# MB_pl_io.net
KiCad netlist of a schematic drawn in Altium Designer
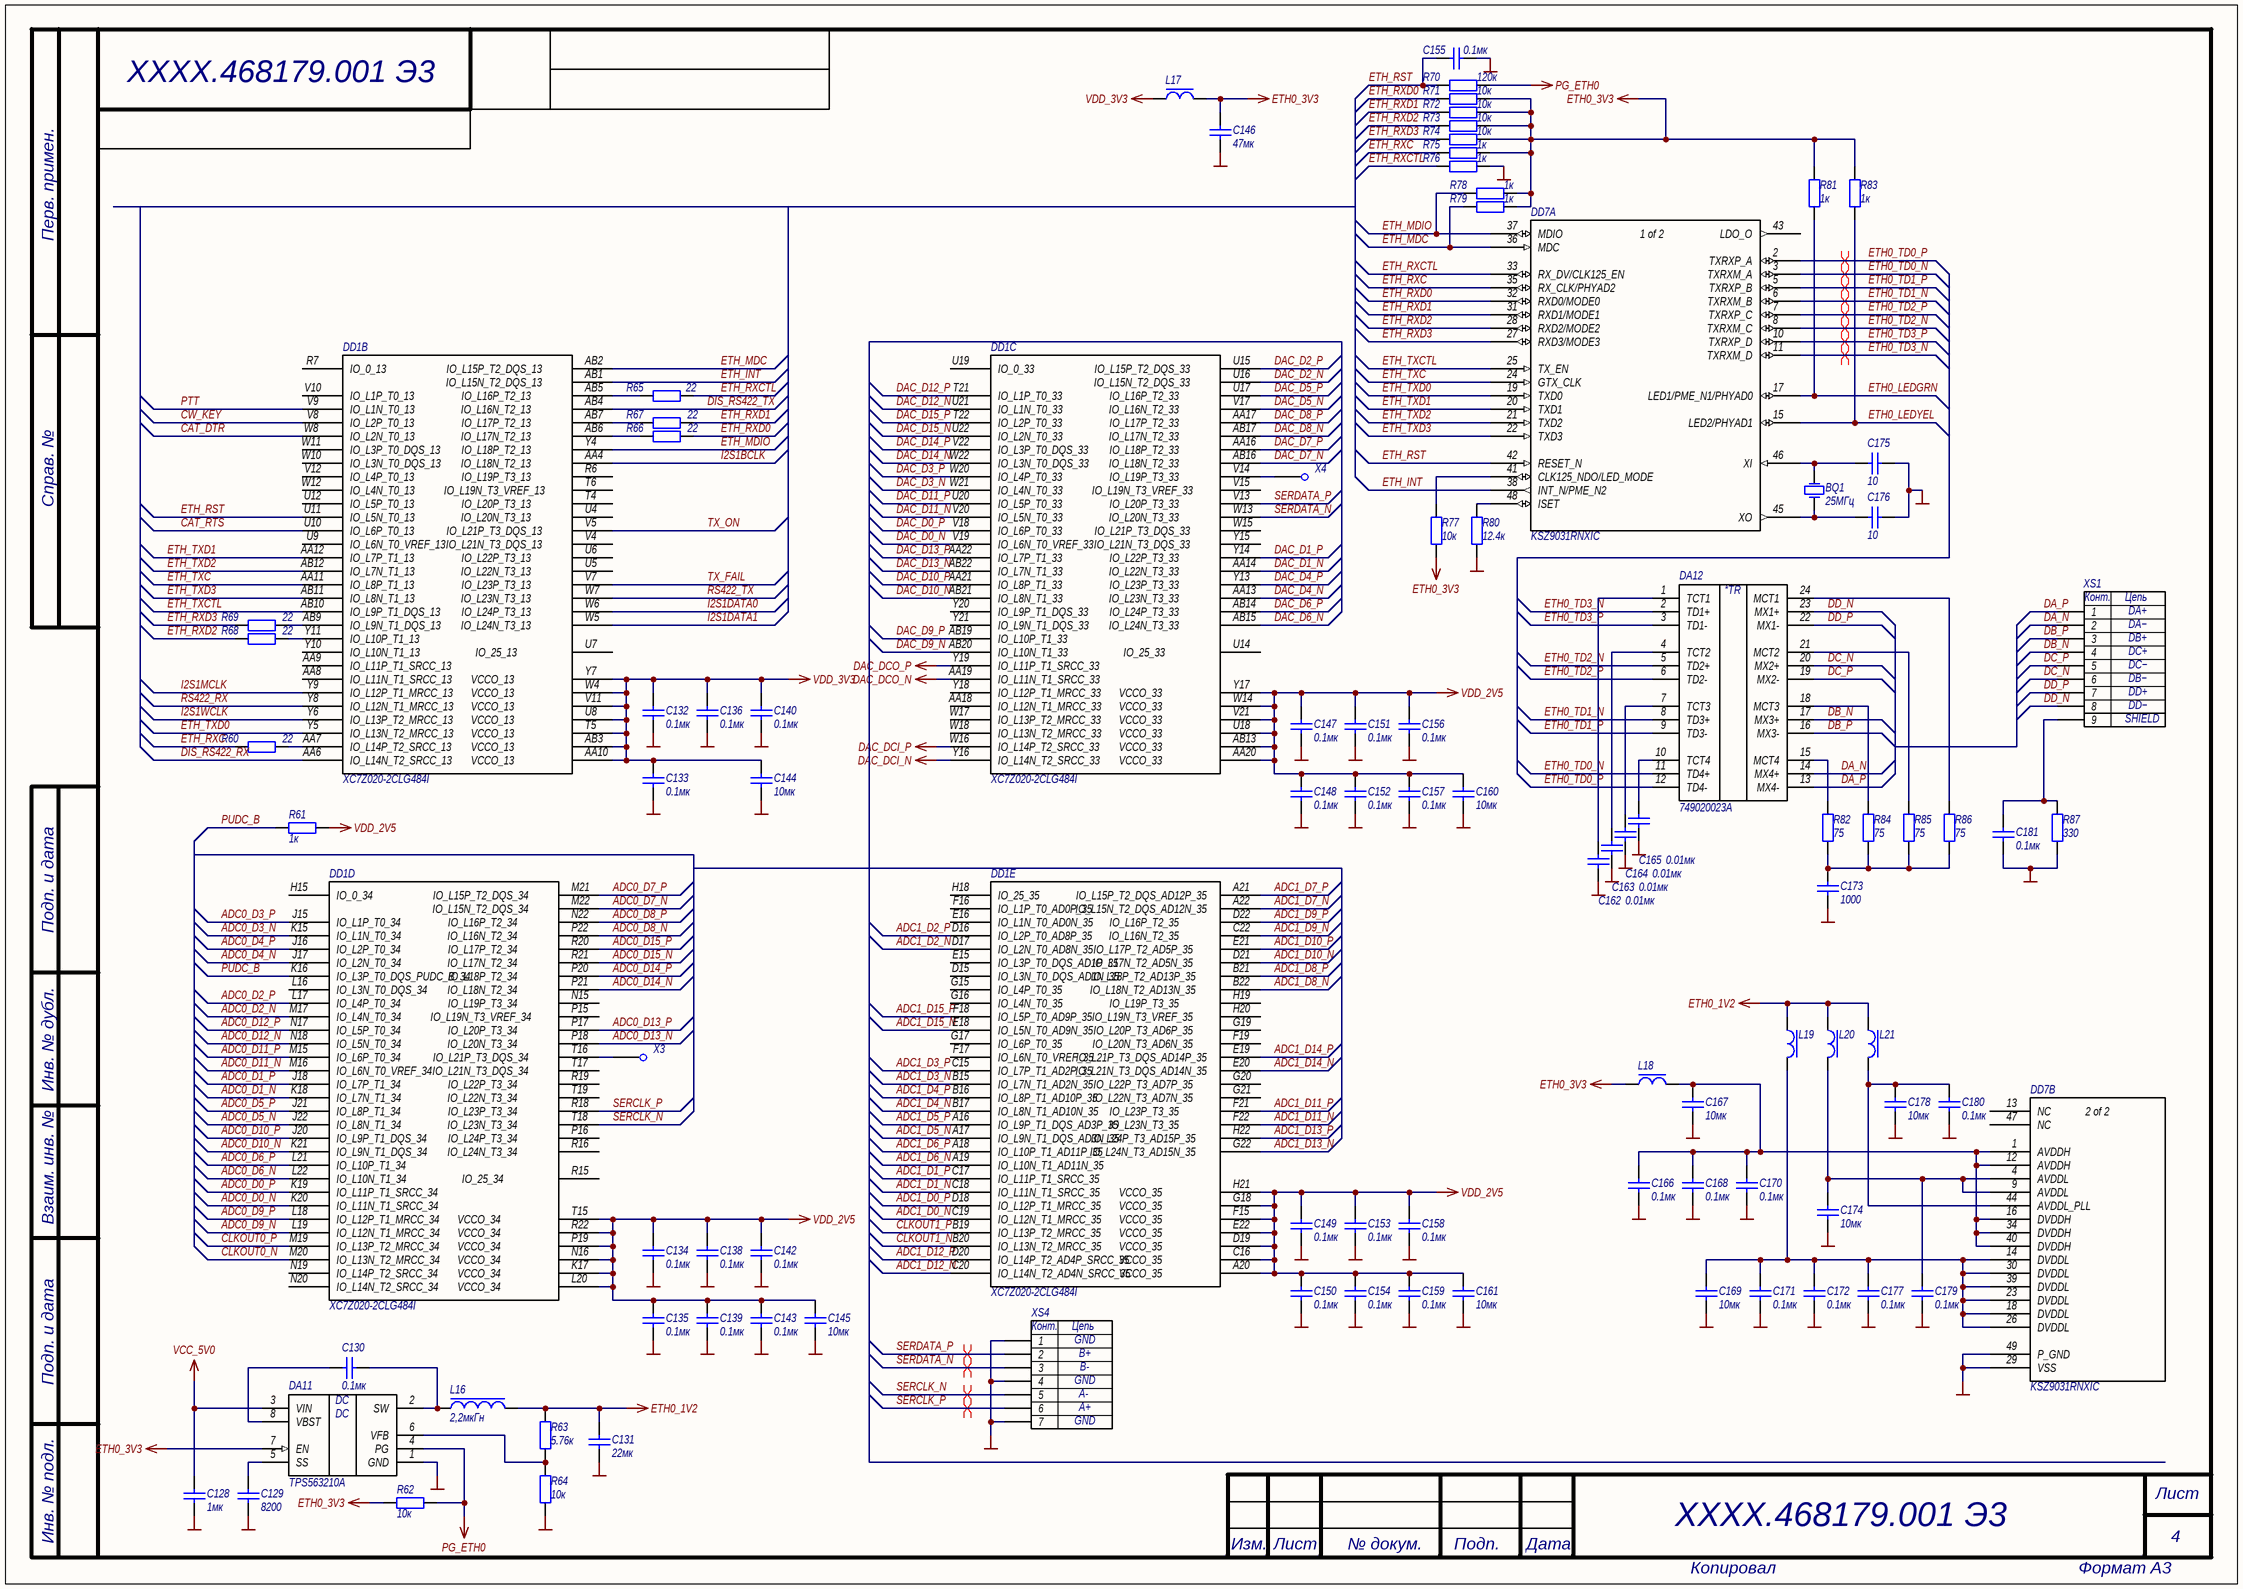
[diagram p0: MB_pl_io.SchDoc]

(export (version "E")
  (design (tool "Eeschema 10.0.6"))
  (components
    (comp (ref "BQ1")
      (value "25МГц")
      (footprint "ABRACOM ABM10")
      (description "Резонатор кварцевый")
      (fields (field (name "TOLERANCE") "±20 ppm") (field (name "MANUFACTURER") "ABRACON"))
      (libsource (lib "nels_other") (part "Кварц ABM10-25.000MHZ-D30"))
    )
    (comp (ref "C128")
      (value "1мк")
      (footprint "CAPC1005X06N")
      (description "Кер. ЧИП-конденсатор")
      (fields (field (name "TOLERANCE") "±10%"))
      (libsource (lib "nels_caps") (part "Кер.ЧИП конд. 0402 1мкФ X5R 10%, 10В"))
    )
    (comp (ref "C129")
      (value "8200")
      (footprint "CAPC1005X06N")
      (description "Кер. ЧИП-конденсатор")
      (fields (field (name "TOLERANCE") "±20%"))
      (libsource (lib "nels_caps") (part "Кер.ЧИП конд. 0402 8200пФ X7R 10%, 50В"))
    )
    (comp (ref "C130")
      (value "0.1мк")
      (footprint "CAPC1005X06N")
      (description "Кер. ЧИП-конденсатор")
      (fields (field (name "TOLERANCE") "±10%"))
      (libsource (lib "nels") (part "Кер.ЧИП конд. 0402 0.1мкФ X7R 10%, 16В"))
    )
    (comp (ref "C131")
      (value "22мк")
      (footprint "CAPC2012X12L")
      (description "Кер. ЧИП-конденсатор")
      (fields (field (name "MANUFACTURER") "TDK") (field (name "TOLERANCE") "±10%"))
      (libsource (lib "nels_caps") (part "Кер.ЧИП конд. 0805 22мкФ X5R 10% 16В"))
    )
    (comp (ref "C132")
      (value "0.1мк")
      (footprint "CAPC1005X06N")
      (description "Кер. ЧИП-конденсатор")
      (fields (field (name "TOLERANCE") "±10%"))
      (libsource (lib "nels") (part "Кер.ЧИП конд. 0402 0.1мкФ X7R 10%, 16В"))
    )
    (comp (ref "C133")
      (value "0.1мк")
      (footprint "CAPC1005X06N")
      (description "Кер. ЧИП-конденсатор")
      (fields (field (name "TOLERANCE") "±10%"))
      (libsource (lib "nels") (part "Кер.ЧИП конд. 0402 0.1мкФ X7R 10%, 16В"))
    )
    (comp (ref "C134")
      (value "0.1мк")
      (footprint "CAPC1005X06N")
      (description "Кер. ЧИП-конденсатор")
      (fields (field (name "TOLERANCE") "±10%"))
      (libsource (lib "nels") (part "Кер.ЧИП конд. 0402 0.1мкФ X7R 10%, 16В"))
    )
    (comp (ref "C135")
      (value "0.1мк")
      (footprint "CAPC1005X06N")
      (description "Кер. ЧИП-конденсатор")
      (fields (field (name "TOLERANCE") "±10%"))
      (libsource (lib "nels") (part "Кер.ЧИП конд. 0402 0.1мкФ X7R 10%, 16В"))
    )
    (comp (ref "C136")
      (value "0.1мк")
      (footprint "CAPC1005X06N")
      (description "Кер. ЧИП-конденсатор")
      (fields (field (name "TOLERANCE") "±10%"))
      (libsource (lib "nels") (part "Кер.ЧИП конд. 0402 0.1мкФ X7R 10%, 16В"))
    )
    (comp (ref "C138")
      (value "0.1мк")
      (footprint "CAPC1005X06N")
      (description "Кер. ЧИП-конденсатор")
      (fields (field (name "TOLERANCE") "±10%"))
      (libsource (lib "nels") (part "Кер.ЧИП конд. 0402 0.1мкФ X7R 10%, 16В"))
    )
    (comp (ref "C139")
      (value "0.1мк")
      (footprint "CAPC1005X06N")
      (description "Кер. ЧИП-конденсатор")
      (fields (field (name "TOLERANCE") "±10%"))
      (libsource (lib "nels") (part "Кер.ЧИП конд. 0402 0.1мкФ X7R 10%, 16В"))
    )
    (comp (ref "C140")
      (value "0.1мк")
      (footprint "CAPC1005X06N")
      (description "Кер. ЧИП-конденсатор")
      (fields (field (name "TOLERANCE") "±10%"))
      (libsource (lib "nels") (part "Кер.ЧИП конд. 0402 0.1мкФ X7R 10%, 16В"))
    )
    (comp (ref "C142")
      (value "0.1мк")
      (footprint "CAPC1005X06N")
      (description "Кер. ЧИП-конденсатор")
      (fields (field (name "TOLERANCE") "±10%"))
      (libsource (lib "nels") (part "Кер.ЧИП конд. 0402 0.1мкФ X7R 10%, 16В"))
    )
    (comp (ref "C143")
      (value "0.1мк")
      (footprint "CAPC1005X06N")
      (description "Кер. ЧИП-конденсатор")
      (fields (field (name "TOLERANCE") "±10%"))
      (libsource (lib "nels") (part "Кер.ЧИП конд. 0402 0.1мкФ X7R 10%, 16В"))
    )
    (comp (ref "C144")
      (value "10мк")
      (footprint "CAPC1608X08L")
      (description "Кер. ЧИП-конденсатор")
      (fields (field (name "MANUFACTURER") "Murata") (field (name "TOLERANCE") "±20%"))
      (libsource (lib "nels_caps") (part "Кер.ЧИП конд. 0603 10мкФ X5R 20% 6.3В"))
    )
    (comp (ref "C145")
      (value "10мк")
      (footprint "CAPC1608X08L")
      (description "Кер. ЧИП-конденсатор")
      (fields (field (name "MANUFACTURER") "Murata") (field (name "TOLERANCE") "±20%"))
      (libsource (lib "nels_caps") (part "Кер.ЧИП конд. 0603 10мкФ X5R 20% 6.3В"))
    )
    (comp (ref "C146")
      (value "47мк")
      (footprint "CAPC2012X12L")
      (description "Кер. ЧИП-конденсатор")
      (fields (field (name "MANUFACTURER") "Murata") (field (name "TOLERANCE") "±20%"))
      (libsource (lib "nels_caps") (part "Кер.ЧИП конд. 0805 47мкФ X5R 20% 10В"))
    )
    (comp (ref "C147")
      (value "0.1мк")
      (footprint "CAPC1005X06N")
      (description "Кер. ЧИП-конденсатор")
      (fields (field (name "TOLERANCE") "±10%"))
      (libsource (lib "nels") (part "Кер.ЧИП конд. 0402 0.1мкФ X7R 10%, 16В"))
    )
    (comp (ref "C148")
      (value "0.1мк")
      (footprint "CAPC1005X06N")
      (description "Кер. ЧИП-конденсатор")
      (fields (field (name "TOLERANCE") "±10%"))
      (libsource (lib "nels") (part "Кер.ЧИП конд. 0402 0.1мкФ X7R 10%, 16В"))
    )
    (comp (ref "C149")
      (value "0.1мк")
      (footprint "CAPC1005X06N")
      (description "Кер. ЧИП-конденсатор")
      (fields (field (name "TOLERANCE") "±10%"))
      (libsource (lib "nels") (part "Кер.ЧИП конд. 0402 0.1мкФ X7R 10%, 16В"))
    )
    (comp (ref "C150")
      (value "0.1мк")
      (footprint "CAPC1005X06N")
      (description "Кер. ЧИП-конденсатор")
      (fields (field (name "TOLERANCE") "±10%"))
      (libsource (lib "nels") (part "Кер.ЧИП конд. 0402 0.1мкФ X7R 10%, 16В"))
    )
    (comp (ref "C151")
      (value "0.1мк")
      (footprint "CAPC1005X06N")
      (description "Кер. ЧИП-конденсатор")
      (fields (field (name "TOLERANCE") "±10%"))
      (libsource (lib "nels") (part "Кер.ЧИП конд. 0402 0.1мкФ X7R 10%, 16В"))
    )
    (comp (ref "C152")
      (value "0.1мк")
      (footprint "CAPC1005X06N")
      (description "Кер. ЧИП-конденсатор")
      (fields (field (name "TOLERANCE") "±10%"))
      (libsource (lib "nels") (part "Кер.ЧИП конд. 0402 0.1мкФ X7R 10%, 16В"))
    )
    (comp (ref "C153")
      (value "0.1мк")
      (footprint "CAPC1005X06N")
      (description "Кер. ЧИП-конденсатор")
      (fields (field (name "TOLERANCE") "±10%"))
      (libsource (lib "nels") (part "Кер.ЧИП конд. 0402 0.1мкФ X7R 10%, 16В"))
    )
    (comp (ref "C154")
      (value "0.1мк")
      (footprint "CAPC1005X06N")
      (description "Кер. ЧИП-конденсатор")
      (fields (field (name "TOLERANCE") "±10%"))
      (libsource (lib "nels") (part "Кер.ЧИП конд. 0402 0.1мкФ X7R 10%, 16В"))
    )
    (comp (ref "C155")
      (value "0.1мк")
      (footprint "CAPC1005X06N")
      (description "Кер. ЧИП-конденсатор")
      (fields (field (name "TOLERANCE") "±10%"))
      (libsource (lib "nels") (part "Кер.ЧИП конд. 0402 0.1мкФ X7R 10%, 16В"))
    )
    (comp (ref "C156")
      (value "0.1мк")
      (footprint "CAPC1005X06N")
      (description "Кер. ЧИП-конденсатор")
      (fields (field (name "TOLERANCE") "±10%"))
      (libsource (lib "nels") (part "Кер.ЧИП конд. 0402 0.1мкФ X7R 10%, 16В"))
    )
    (comp (ref "C157")
      (value "0.1мк")
      (footprint "CAPC1005X06N")
      (description "Кер. ЧИП-конденсатор")
      (fields (field (name "TOLERANCE") "±10%"))
      (libsource (lib "nels") (part "Кер.ЧИП конд. 0402 0.1мкФ X7R 10%, 16В"))
    )
    (comp (ref "C158")
      (value "0.1мк")
      (footprint "CAPC1005X06N")
      (description "Кер. ЧИП-конденсатор")
      (fields (field (name "TOLERANCE") "±10%"))
      (libsource (lib "nels") (part "Кер.ЧИП конд. 0402 0.1мкФ X7R 10%, 16В"))
    )
    (comp (ref "C159")
      (value "0.1мк")
      (footprint "CAPC1005X06N")
      (description "Кер. ЧИП-конденсатор")
      (fields (field (name "TOLERANCE") "±10%"))
      (libsource (lib "nels") (part "Кер.ЧИП конд. 0402 0.1мкФ X7R 10%, 16В"))
    )
    (comp (ref "C160")
      (value "10мк")
      (footprint "CAPC1608X08L")
      (description "Кер. ЧИП-конденсатор")
      (fields (field (name "MANUFACTURER") "Murata") (field (name "TOLERANCE") "±20%"))
      (libsource (lib "nels_caps") (part "Кер.ЧИП конд. 0603 10мкФ X5R 20% 6.3В"))
    )
    (comp (ref "C161")
      (value "10мк")
      (footprint "CAPC1608X08L")
      (description "Кер. ЧИП-конденсатор")
      (fields (field (name "MANUFACTURER") "Murata") (field (name "TOLERANCE") "±20%"))
      (libsource (lib "nels_caps") (part "Кер.ЧИП конд. 0603 10мкФ X5R 20% 6.3В"))
    )
    (comp (ref "C162")
      (value "0.01мк")
      (footprint "CAPC1005X06N")
      (description "Кер. ЧИП-конденсатор")
      (fields (field (name "TOLERANCE") "±20%"))
      (libsource (lib "nels_caps") (part "Кер.ЧИП конд. 0402 0.01мкФ X7R 10%, 50В"))
    )
    (comp (ref "C163")
      (value "0.01мк")
      (footprint "CAPC1005X06N")
      (description "Кер. ЧИП-конденсатор")
      (fields (field (name "TOLERANCE") "±20%"))
      (libsource (lib "nels_caps") (part "Кер.ЧИП конд. 0402 0.01мкФ X7R 10%, 50В"))
    )
    (comp (ref "C164")
      (value "0.01мк")
      (footprint "CAPC1005X06N")
      (description "Кер. ЧИП-конденсатор")
      (fields (field (name "TOLERANCE") "±20%"))
      (libsource (lib "nels_caps") (part "Кер.ЧИП конд. 0402 0.01мкФ X7R 10%, 50В"))
    )
    (comp (ref "C165")
      (value "0.01мк")
      (footprint "CAPC1005X06N")
      (description "Кер. ЧИП-конденсатор")
      (fields (field (name "TOLERANCE") "±20%"))
      (libsource (lib "nels_caps") (part "Кер.ЧИП конд. 0402 0.01мкФ X7R 10%, 50В"))
    )
    (comp (ref "C166")
      (value "0.1мк")
      (footprint "CAPC1005X06N")
      (description "Кер. ЧИП-конденсатор")
      (fields (field (name "TOLERANCE") "±10%"))
      (libsource (lib "nels_caps") (part "Кер.ЧИП конд. 0402 0.1мкФ X7R 10%, 16В"))
    )
    (comp (ref "C167")
      (value "10мк")
      (footprint "CAPC1608X08L")
      (description "Кер. ЧИП-конденсатор")
      (fields (field (name "MANUFACTURER") "Murata") (field (name "TOLERANCE") "±20%"))
      (libsource (lib "nels_caps") (part "Кер.ЧИП конд. 0603 10мкФ X5R 20% 6.3В"))
    )
    (comp (ref "C168")
      (value "0.1мк")
      (footprint "CAPC1005X06N")
      (description "Кер. ЧИП-конденсатор")
      (fields (field (name "TOLERANCE") "±10%"))
      (libsource (lib "nels_caps") (part "Кер.ЧИП конд. 0402 0.1мкФ X7R 10%, 16В"))
    )
    (comp (ref "C169")
      (value "10мк")
      (footprint "CAPC1608X08L")
      (description "Кер. ЧИП-конденсатор")
      (fields (field (name "MANUFACTURER") "Murata") (field (name "TOLERANCE") "±20%"))
      (libsource (lib "nels_caps") (part "Кер.ЧИП конд. 0603 10мкФ X5R 20% 6.3В"))
    )
    (comp (ref "C170")
      (value "0.1мк")
      (footprint "CAPC1005X06N")
      (description "Кер. ЧИП-конденсатор")
      (fields (field (name "TOLERANCE") "±10%"))
      (libsource (lib "nels_caps") (part "Кер.ЧИП конд. 0402 0.1мкФ X7R 10%, 16В"))
    )
    (comp (ref "C171")
      (value "0.1мк")
      (footprint "CAPC1005X06N")
      (description "Кер. ЧИП-конденсатор")
      (fields (field (name "TOLERANCE") "±10%"))
      (libsource (lib "nels_caps") (part "Кер.ЧИП конд. 0402 0.1мкФ X7R 10%, 16В"))
    )
    (comp (ref "C172")
      (value "0.1мк")
      (footprint "CAPC1005X06N")
      (description "Кер. ЧИП-конденсатор")
      (fields (field (name "TOLERANCE") "±10%"))
      (libsource (lib "nels_caps") (part "Кер.ЧИП конд. 0402 0.1мкФ X7R 10%, 16В"))
    )
    (comp (ref "C173")
      (value "1000")
      (footprint "CAPC1005X06N")
      (description "Кер. ЧИП-конденсатор")
      (fields (field (name "TOLERANCE") "±5%"))
      (libsource (lib "nels_caps") (part "Кер.ЧИП конд. 0402 1000пФ NP0 5%, 50В"))
    )
    (comp (ref "C174")
      (value "10мк")
      (footprint "CAPC1608X08L")
      (description "Кер. ЧИП-конденсатор")
      (fields (field (name "MANUFACTURER") "Murata") (field (name "TOLERANCE") "±20%"))
      (libsource (lib "nels_caps") (part "Кер.ЧИП конд. 0603 10мкФ X5R 20% 6.3В"))
    )
    (comp (ref "C175")
      (value "10")
      (footprint "CAPC1005X06N")
      (description "Кер. ЧИП-конденсатор")
      (fields (field (name "TOLERANCE") "±5%"))
      (libsource (lib "nels_caps") (part "Кер.ЧИП конд. 0402 10пФ NPO 5%, 50В"))
    )
    (comp (ref "C176")
      (value "10")
      (footprint "CAPC1005X06N")
      (description "Кер. ЧИП-конденсатор")
      (fields (field (name "TOLERANCE") "±5%"))
      (libsource (lib "nels_caps") (part "Кер.ЧИП конд. 0402 10пФ NPO 5%, 50В"))
    )
    (comp (ref "C177")
      (value "0.1мк")
      (footprint "CAPC1005X06N")
      (description "Кер. ЧИП-конденсатор")
      (fields (field (name "TOLERANCE") "±10%"))
      (libsource (lib "nels_caps") (part "Кер.ЧИП конд. 0402 0.1мкФ X7R 10%, 16В"))
    )
    (comp (ref "C178")
      (value "10мк")
      (footprint "CAPC1608X08L")
      (description "Кер. ЧИП-конденсатор")
      (fields (field (name "MANUFACTURER") "Murata") (field (name "TOLERANCE") "±20%"))
      (libsource (lib "nels_caps") (part "Кер.ЧИП конд. 0603 10мкФ X5R 20% 6.3В"))
    )
    (comp (ref "C179")
      (value "0.1мк")
      (footprint "CAPC1005X06N")
      (description "Кер. ЧИП-конденсатор")
      (fields (field (name "TOLERANCE") "±10%"))
      (libsource (lib "nels_caps") (part "Кер.ЧИП конд. 0402 0.1мкФ X7R 10%, 16В"))
    )
    (comp (ref "C180")
      (value "0.1мк")
      (footprint "CAPC1005X06N")
      (description "Кер. ЧИП-конденсатор")
      (fields (field (name "TOLERANCE") "±10%"))
      (libsource (lib "nels_caps") (part "Кер.ЧИП конд. 0402 0.1мкФ X7R 10%, 16В"))
    )
    (comp (ref "C181")
      (value "0.1мк")
      (footprint "CAPC1608X08L")
      (description "Кер. ЧИП-конденсатор")
      (fields (field (name "TOLERANCE") "±10%") (field (name "MANUFACTURER") "Murata"))
      (libsource (lib "nels_caps") (part "Кер.ЧИП конд. 0603 0.1мкФ X7R 10% 50В"))
    )
    (comp (ref "DA11")
      (value "TPS563210A")
      (footprint "TSOP65P280X110-8N")
      (description "TPS56x210A, 4.5-V to 17-V Input, 2-A, 3-A Synchrono")
      (fields (field (name "MANUFACTURER") "TI"))
      (libsource (lib "MB") (part "Микросхема TPS563210A"))
    )
    (comp (ref "DA12")
      (value "749020023A")
      (footprint "749020023A")
      (description "1000BASE-T Magnetics Module")
      (fields (field (name "MANUFACTURER") "Wurth Elektronik"))
      (libsource (lib "nels_other") (part "Сборка трансформаторов 749020023A"))
    )
    (comp (ref "DD1")
      (value "XC7Z020-2CLG484I")
      (footprint "BGA484C80P22X22_1900X1900X160")
      (description "Zynq®-7000 SoC Family")
      (fields (field (name "MANUFACTURER") "XILINX"))
      (libsource (lib "MB") (part "Микросхема XC7Z020-2CLG484I"))
    )
    (comp (ref "DD7")
      (value "KSZ9031RNXIC")
      (footprint "QFN50P700X700-48V6M")
      (description "Gigabit Ethernet Transceiver with Power Saving Features")
      (fields (field (name "COPYRIGHT") "Copyright (C) 2018 Accelerated Designs. All rights reserved"))
      (libsource (lib "nels_chip") (part "Микросхема KSZ9031RNXIC"))
    )
    (comp (ref "L16")
      (value "2,2мкГн")
      (footprint "CSAB0420")
      (description "Molding Power Choke")
      (fields
        (field (name "MANUFACTURER") "Vishay")
        (field (name "MANUFACTURERPARTNUMBER") "IHLP1616ABER1R0M11")
      )
      (libsource (lib "nels_ind") (part "ЧИП индуктивность CSAB0420-2R2M"))
    )
    (comp (ref "L17")
      (value "BLM18PG121SN1D")
      (footprint "INDC1608X08L")
      (description "SMD EMI Suppression Filter EMIFIL")
      (fields (field (name "MANUFACTURER") "Murata"))
      (libsource (lib "nels_ind") (part "ЧИП дроссель 0603 BLM18PG121SN1D"))
    )
    (comp (ref "L18")
      (value "BLM18PG121SN1D")
      (footprint "INDC1608X08L")
      (description "SMD EMI Suppression Filter EMIFIL")
      (fields (field (name "MANUFACTURER") "Murata"))
      (libsource (lib "nels_ind") (part "ЧИП дроссель 0603 BLM18PG121SN1D"))
    )
    (comp (ref "L19")
      (value "BLM18PG121SN1D")
      (footprint "INDC1608X08L")
      (description "SMD EMI Suppression Filter EMIFIL")
      (fields (field (name "MANUFACTURER") "Murata"))
      (libsource (lib "nels_ind") (part "ЧИП дроссель 0603 BLM18PG121SN1D"))
    )
    (comp (ref "L20")
      (value "BLM18PG121SN1D")
      (footprint "INDC1608X08L")
      (description "SMD EMI Suppression Filter EMIFIL")
      (fields (field (name "MANUFACTURER") "Murata"))
      (libsource (lib "nels_ind") (part "ЧИП дроссель 0603 BLM18PG121SN1D"))
    )
    (comp (ref "L21")
      (value "BLM18PG121SN1D")
      (footprint "INDC1608X08L")
      (description "SMD EMI Suppression Filter EMIFIL")
      (fields (field (name "MANUFACTURER") "Murata"))
      (libsource (lib "nels_ind") (part "ЧИП дроссель 0603 BLM18PG121SN1D"))
    )
    (comp (ref "R60")
      (value "22")
      (footprint "RESC1005X06N")
      (description "ЧИП-резистор")
      (fields (field (name "TOLERANCE") "±5%"))
      (libsource (lib "nels_res") (part "Чип резистор 0402 22 Ом, 5%"))
    )
    (comp (ref "R61")
      (value "1к")
      (footprint "RESC1005X06N")
      (description "ЧИП-резистор")
      (fields (field (name "TOLERANCE") "±5%"))
      (libsource (lib "") (part "Чип резистор 0402 1 кОм, 5%_1"))
    )
    (comp (ref "R62")
      (value "10к")
      (footprint "RESC1005X06N")
      (description "ЧИП-резистор")
      (fields (field (name "TOLERANCE") "±5%"))
      (libsource (lib "nels_res") (part "Чип резистор 0402 10 кОм, 1%"))
    )
    (comp (ref "R63")
      (value "5.76к")
      (footprint "RESC1005X06N")
      (description "ЧИП-резистор")
      (fields (field (name "TOLERANCE") "±1%"))
      (libsource (lib "nels_res") (part "Чип резистор 0402 5,76 кОм, 1%"))
    )
    (comp (ref "R64")
      (value "10к")
      (footprint "RESC1005X06N")
      (description "ЧИП-резистор")
      (fields (field (name "TOLERANCE") "±5%"))
      (libsource (lib "nels_res") (part "Чип резистор 0402 10 кОм, 5%"))
    )
    (comp (ref "R65")
      (value "22")
      (footprint "RESC1005X06N")
      (description "ЧИП-резистор")
      (fields (field (name "TOLERANCE") "±5%"))
      (libsource (lib "") (part "Чип резистор 0402 22 Ом, 5%_1"))
    )
    (comp (ref "R66")
      (value "22")
      (footprint "RESC1005X06N")
      (description "ЧИП-резистор")
      (fields (field (name "TOLERANCE") "±5%"))
      (libsource (lib "nels_res") (part "Чип резистор 0402 22 Ом, 5%"))
    )
    (comp (ref "R67")
      (value "22")
      (footprint "RESC1005X06N")
      (description "ЧИП-резистор")
      (fields (field (name "TOLERANCE") "±5%"))
      (libsource (lib "nels_res") (part "Чип резистор 0402 22 Ом, 5%"))
    )
    (comp (ref "R68")
      (value "22")
      (footprint "RESC1005X06N")
      (description "ЧИП-резистор")
      (fields (field (name "TOLERANCE") "±5%"))
      (libsource (lib "nels_res") (part "Чип резистор 0402 22 Ом, 5%"))
    )
    (comp (ref "R69")
      (value "22")
      (footprint "RESC1005X06N")
      (description "ЧИП-резистор")
      (fields (field (name "TOLERANCE") "±5%"))
      (libsource (lib "nels_res") (part "Чип резистор 0402 22 Ом, 5%"))
    )
    (comp (ref "R70")
      (value "120к")
      (footprint "RESC1005X06N")
      (description "ЧИП-резистор")
      (fields (field (name "TOLERANCE") "±5%"))
      (libsource (lib "nels_res") (part "Чип резистор 0402 120 кОм, 5%"))
    )
    (comp (ref "R71")
      (value "10к")
      (footprint "RESC1005X06N")
      (description "ЧИП-резистор")
      (fields (field (name "TOLERANCE") "±5%"))
      (libsource (lib "") (part "Чип резистор 0402 10 кОм, 5%_1"))
    )
    (comp (ref "R72")
      (value "10к")
      (footprint "RESC1005X06N")
      (description "ЧИП-резистор")
      (fields (field (name "TOLERANCE") "±5%"))
      (libsource (lib "") (part "Чип резистор 0402 10 кОм, 5%_1"))
    )
    (comp (ref "R73")
      (value "10к")
      (footprint "RESC1005X06N")
      (description "ЧИП-резистор")
      (fields (field (name "TOLERANCE") "±5%"))
      (libsource (lib "") (part "Чип резистор 0402 10 кОм, 5%_1"))
    )
    (comp (ref "R74")
      (value "10к")
      (footprint "RESC1005X06N")
      (description "ЧИП-резистор")
      (fields (field (name "TOLERANCE") "±5%"))
      (libsource (lib "") (part "Чип резистор 0402 10 кОм, 5%_1"))
    )
    (comp (ref "R75")
      (value "1к")
      (footprint "RESC1005X06N")
      (description "ЧИП-резистор")
      (fields (field (name "TOLERANCE") "±5%"))
      (libsource (lib "") (part "Чип резистор 0402 1 кОм, 5%_1"))
    )
    (comp (ref "R76")
      (value "1к")
      (footprint "RESC1005X06N")
      (description "ЧИП-резистор")
      (fields (field (name "TOLERANCE") "±5%"))
      (libsource (lib "") (part "Чип резистор 0402 1 кОм, 5%_1"))
    )
    (comp (ref "R77")
      (value "10к")
      (footprint "RESC1005X06N")
      (description "ЧИП-резистор")
      (fields (field (name "TOLERANCE") "±5%"))
      (libsource (lib "nels_res") (part "Чип резистор 0402 10 кОм, 5%"))
    )
    (comp (ref "R78")
      (value "1к")
      (footprint "RESC1005X06N")
      (description "ЧИП-резистор")
      (fields (field (name "TOLERANCE") "±5%"))
      (libsource (lib "") (part "Чип резистор 0402 1 кОм, 5%_1"))
    )
    (comp (ref "R79")
      (value "1к")
      (footprint "RESC1005X06N")
      (description "ЧИП-резистор")
      (fields (field (name "TOLERANCE") "±5%"))
      (libsource (lib "") (part "Чип резистор 0402 1 кОм, 5%_1"))
    )
    (comp (ref "R80")
      (value "12.4к")
      (footprint "RESC1005X06N")
      (description "ЧИП-резистор")
      (fields (field (name "TOLERANCE") "±1%"))
      (libsource (lib "nels_res") (part "Чип резистор 0402 12.4 кОм, 1%"))
    )
    (comp (ref "R81")
      (value "1к")
      (footprint "RESC1005X06N")
      (description "ЧИП-резистор")
      (fields (field (name "TOLERANCE") "±5%"))
      (libsource (lib "nels_res") (part "Чип резистор 0402 1 кОм, 5%"))
    )
    (comp (ref "R82")
      (value "75")
      (footprint "RESC1005X06N")
      (description "ЧИП-резистор")
      (fields (field (name "TOLERANCE") "±5%"))
      (libsource (lib "nels_res") (part "Чип резистор 0402 75 Ом, 5%"))
    )
    (comp (ref "R83")
      (value "1к")
      (footprint "RESC1005X06N")
      (description "ЧИП-резистор")
      (fields (field (name "TOLERANCE") "±5%"))
      (libsource (lib "nels_res") (part "Чип резистор 0402 1 кОм, 5%"))
    )
    (comp (ref "R84")
      (value "75")
      (footprint "RESC1005X06N")
      (description "ЧИП-резистор")
      (fields (field (name "TOLERANCE") "±5%"))
      (libsource (lib "nels_res") (part "Чип резистор 0402 75 Ом, 5%"))
    )
    (comp (ref "R85")
      (value "75")
      (footprint "RESC1005X06N")
      (description "ЧИП-резистор")
      (fields (field (name "TOLERANCE") "±5%"))
      (libsource (lib "nels_res") (part "Чип резистор 0402 75 Ом, 5%"))
    )
    (comp (ref "R86")
      (value "75")
      (footprint "RESC1005X06N")
      (description "ЧИП-резистор")
      (fields (field (name "TOLERANCE") "±5%"))
      (libsource (lib "nels_res") (part "Чип резистор 0402 75 Ом, 5%"))
    )
    (comp (ref "R87")
      (value "330")
      (footprint "RESC1005X06N")
      (description "ЧИП-резистор")
      (fields (field (name "TOLERANCE") "±5%"))
      (libsource (lib "nels_res") (part "Чип резистор 0402 330 Ом, 5%"))
    )
    (comp (ref "X3")
      (value "Конструктивный элемент")
      (footprint "PIN2_PROBE")
      (description "Соединитель")
      (libsource (lib "nels_conn") (part "Соединение под пайку"))
    )
    (comp (ref "X4")
      (value "Конструктивный элемент")
      (footprint "PIN2_PROBE")
      (description "Соединитель")
      (libsource (lib "nels_conn") (part "Соединение под пайку"))
    )
    (comp (ref "XS1")
      (value "TJ16S-8P8C")
      (footprint "KLS12-107L")
      (description "Modular Jack RJ45")
      (fields (field (name "MANUFACTURER") "KLS"))
      (libsource (lib "nels_conn") (part "Соединитель KLS12-107L-2-8P8C-0"))
    )
    (comp (ref "XS4")
      (value "KLS1-SATA001")
      (footprint "KLS1-SATA001")
      (description "SATA Type A 7P Male Connector,SMD")
      (fields (field (name "MANUFACTURER") "KLS"))
      (libsource (lib "nels_conn") (part "Соединитель KLS1-SATA001"))
    )
  )
  (nets
    (net (code "1") (name "/ADC0_D0_N") (class "Default")
      (node (ref "DD1") (pin "K20") (pinfunction "IO_L11N_T1_SRCC_34_K20") (pintype "passive"))
    )
    (net (code "2") (name "/ADC0_D0_P") (class "Default")
      (node (ref "DD1") (pin "K19") (pinfunction "IO_L11P_T1_SRCC_34_K19") (pintype "passive"))
    )
    (net (code "3") (name "/ADC0_D1_N") (class "Default")
      (node (ref "DD1") (pin "K18") (pinfunction "IO_L7N_T1_34_K18") (pintype "passive"))
    )
    (net (code "4") (name "/ADC0_D1_P") (class "Default")
      (node (ref "DD1") (pin "J18") (pinfunction "IO_L7P_T1_34_J18") (pintype "passive"))
    )
    (net (code "5") (name "/ADC0_D2_N") (class "Default")
      (node (ref "DD1") (pin "M17") (pinfunction "IO_L4N_T0_34_M17") (pintype "passive"))
    )
    (net (code "6") (name "/ADC0_D2_P") (class "Default")
      (node (ref "DD1") (pin "L17") (pinfunction "IO_L4P_T0_34_L17") (pintype "passive"))
    )
    (net (code "7") (name "/ADC0_D3_N") (class "Default")
      (node (ref "DD1") (pin "K15") (pinfunction "IO_L1N_T0_34_K15") (pintype "passive"))
    )
    (net (code "8") (name "/ADC0_D3_P") (class "Default")
      (node (ref "DD1") (pin "J15") (pinfunction "IO_L1P_T0_34_J15") (pintype "passive"))
    )
    (net (code "9") (name "/ADC0_D4_N") (class "Default")
      (node (ref "DD1") (pin "J17") (pinfunction "IO_L2N_T0_34_J17") (pintype "passive"))
    )
    (net (code "10") (name "/ADC0_D4_P") (class "Default")
      (node (ref "DD1") (pin "J16") (pinfunction "IO_L2P_T0_34_J16") (pintype "passive"))
    )
    (net (code "11") (name "/ADC0_D5_N") (class "Default")
      (node (ref "DD1") (pin "J22") (pinfunction "IO_L8N_T1_34_J22") (pintype "passive"))
    )
    (net (code "12") (name "/ADC0_D5_P") (class "Default")
      (node (ref "DD1") (pin "J21") (pinfunction "IO_L8P_T1_34_J21") (pintype "passive"))
    )
    (net (code "13") (name "/ADC0_D6_N") (class "Default")
      (node (ref "DD1") (pin "L22") (pinfunction "IO_L10N_T1_34_L22") (pintype "passive"))
    )
    (net (code "14") (name "/ADC0_D6_P") (class "Default")
      (node (ref "DD1") (pin "L21") (pinfunction "IO_L10P_T1_34_L21") (pintype "passive"))
    )
    (net (code "15") (name "/ADC0_D7_N") (class "Default")
      (node (ref "DD1") (pin "M22") (pinfunction "IO_L15N_T2_DQS_34_M22") (pintype "passive"))
    )
    (net (code "16") (name "/ADC0_D7_P") (class "Default")
      (node (ref "DD1") (pin "M21") (pinfunction "IO_L15P_T2_DQS_34_M21") (pintype "passive"))
    )
    (net (code "17") (name "/ADC0_D8_N") (class "Default")
      (node (ref "DD1") (pin "P22") (pinfunction "IO_L16N_T2_34_P22") (pintype "passive"))
    )
    (net (code "18") (name "/ADC0_D8_P") (class "Default")
      (node (ref "DD1") (pin "N22") (pinfunction "IO_L16P_T2_34_N22") (pintype "passive"))
    )
    (net (code "19") (name "/ADC0_D9_N") (class "Default")
      (node (ref "DD1") (pin "L19") (pinfunction "IO_L12N_T1_MRCC_34_L19") (pintype "passive"))
    )
    (net (code "20") (name "/ADC0_D9_P") (class "Default")
      (node (ref "DD1") (pin "L18") (pinfunction "IO_L12P_T1_MRCC_34_L18") (pintype "passive"))
    )
    (net (code "21") (name "/ADC0_D10_N") (class "Default")
      (node (ref "DD1") (pin "K21") (pinfunction "IO_L9N_T1_DQS_34_K21") (pintype "passive"))
    )
    (net (code "22") (name "/ADC0_D10_P") (class "Default")
      (node (ref "DD1") (pin "J20") (pinfunction "IO_L9P_T1_DQS_34_J20") (pintype "passive"))
    )
    (net (code "23") (name "/ADC0_D11_N") (class "Default")
      (node (ref "DD1") (pin "M16") (pinfunction "IO_L6N_T0_VREF_34_M16") (pintype "passive"))
    )
    (net (code "24") (name "/ADC0_D11_P") (class "Default")
      (node (ref "DD1") (pin "M15") (pinfunction "IO_L6P_T0_34_M15") (pintype "passive"))
    )
    (net (code "25") (name "/ADC0_D12_N") (class "Default")
      (node (ref "DD1") (pin "N18") (pinfunction "IO_L5N_T0_34_N18") (pintype "passive"))
    )
    (net (code "26") (name "/ADC0_D12_P") (class "Default")
      (node (ref "DD1") (pin "N17") (pinfunction "IO_L5P_T0_34_N17") (pintype "passive"))
    )
    (net (code "27") (name "/ADC0_D13_N") (class "Default")
      (node (ref "DD1") (pin "P18") (pinfunction "IO_L20N_T3_34_P18") (pintype "passive"))
    )
    (net (code "28") (name "/ADC0_D13_P") (class "Default")
      (node (ref "DD1") (pin "P17") (pinfunction "IO_L20P_T3_34_P17") (pintype "passive"))
    )
    (net (code "29") (name "/ADC0_D14_N") (class "Default")
      (node (ref "DD1") (pin "P21") (pinfunction "IO_L18N_T2_34_P21") (pintype "passive"))
    )
    (net (code "30") (name "/ADC0_D14_P") (class "Default")
      (node (ref "DD1") (pin "P20") (pinfunction "IO_L18P_T2_34_P20") (pintype "passive"))
    )
    (net (code "31") (name "/ADC0_D15_N") (class "Default")
      (node (ref "DD1") (pin "R21") (pinfunction "IO_L17N_T2_34_R21") (pintype "passive"))
    )
    (net (code "32") (name "/ADC0_D15_P") (class "Default")
      (node (ref "DD1") (pin "R20") (pinfunction "IO_L17P_T2_34_R20") (pintype "passive"))
    )
    (net (code "33") (name "/ADC1_D0_N") (class "Default")
      (node (ref "DD1") (pin "C19") (pinfunction "IO_L12N_T1_MRCC_35_C19") (pintype "passive"))
    )
    (net (code "34") (name "/ADC1_D0_P") (class "Default")
      (node (ref "DD1") (pin "D18") (pinfunction "IO_L12P_T1_MRCC_35_D18") (pintype "passive"))
    )
    (net (code "35") (name "/ADC1_D1_N") (class "Default")
      (node (ref "DD1") (pin "C18") (pinfunction "IO_L11N_T1_SRCC_35_C18") (pintype "passive"))
    )
    (net (code "36") (name "/ADC1_D1_P") (class "Default")
      (node (ref "DD1") (pin "C17") (pinfunction "IO_L11P_T1_SRCC_35_C17") (pintype "passive"))
    )
    (net (code "37") (name "/ADC1_D2_N") (class "Default")
      (node (ref "DD1") (pin "D17") (pinfunction "IO_L2N_T0_AD8N_35_D17") (pintype "passive"))
    )
    (net (code "38") (name "/ADC1_D2_P") (class "Default")
      (node (ref "DD1") (pin "D16") (pinfunction "IO_L2P_T0_AD8P_35_D16") (pintype "passive"))
    )
    (net (code "39") (name "/ADC1_D3_N") (class "Default")
      (node (ref "DD1") (pin "B15") (pinfunction "IO_L7N_T1_AD2N_35_B15") (pintype "passive"))
    )
    (net (code "40") (name "/ADC1_D3_P") (class "Default")
      (node (ref "DD1") (pin "C15") (pinfunction "IO_L7P_T1_AD2P_35_C15") (pintype "passive"))
    )
    (net (code "41") (name "/ADC1_D4_N") (class "Default")
      (node (ref "DD1") (pin "B17") (pinfunction "IO_L8N_T1_AD10N_35_B17") (pintype "passive"))
    )
    (net (code "42") (name "/ADC1_D4_P") (class "Default")
      (node (ref "DD1") (pin "B16") (pinfunction "IO_L8P_T1_AD10P_35_B16") (pintype "passive"))
    )
    (net (code "43") (name "/ADC1_D5_N") (class "Default")
      (node (ref "DD1") (pin "A17") (pinfunction "IO_L9N_T1_DQS_AD3N_35_A17") (pintype "passive"))
    )
    (net (code "44") (name "/ADC1_D5_P") (class "Default")
      (node (ref "DD1") (pin "A16") (pinfunction "IO_L9P_T1_DQS_AD3P_35_A16") (pintype "passive"))
    )
    (net (code "45") (name "/ADC1_D6_N") (class "Default")
      (node (ref "DD1") (pin "A19") (pinfunction "IO_L10N_T1_AD11N_35_A19") (pintype "passive"))
    )
    (net (code "46") (name "/ADC1_D6_P") (class "Default")
      (node (ref "DD1") (pin "A18") (pinfunction "IO_L10P_T1_AD11P_35_A18") (pintype "passive"))
    )
    (net (code "47") (name "/ADC1_D7_N") (class "Default")
      (node (ref "DD1") (pin "A22") (pinfunction "IO_L15N_T2_DQS_AD12N_35_A22") (pintype "passive"))
    )
    (net (code "48") (name "/ADC1_D7_P") (class "Default")
      (node (ref "DD1") (pin "A21") (pinfunction "IO_L15P_T2_DQS_AD12P_35_A21") (pintype "passive"))
    )
    (net (code "49") (name "/ADC1_D8_N") (class "Default")
      (node (ref "DD1") (pin "B22") (pinfunction "IO_L18N_T2_AD13N_35_B22") (pintype "passive"))
    )
    (net (code "50") (name "/ADC1_D8_P") (class "Default")
      (node (ref "DD1") (pin "B21") (pinfunction "IO_L18P_T2_AD13P_35_B21") (pintype "passive"))
    )
    (net (code "51") (name "/ADC1_D9_N") (class "Default")
      (node (ref "DD1") (pin "C22") (pinfunction "IO_L16N_T2_35_C22") (pintype "passive"))
    )
    (net (code "52") (name "/ADC1_D9_P") (class "Default")
      (node (ref "DD1") (pin "D22") (pinfunction "IO_L16P_T2_35_D22") (pintype "passive"))
    )
    (net (code "53") (name "/ADC1_D10_N") (class "Default")
      (node (ref "DD1") (pin "D21") (pinfunction "IO_L17N_T2_AD5N_35_D21") (pintype "passive"))
    )
    (net (code "54") (name "/ADC1_D10_P") (class "Default")
      (node (ref "DD1") (pin "E21") (pinfunction "IO_L17P_T2_AD5P_35_E21") (pintype "passive"))
    )
    (net (code "55") (name "/ADC1_D11_N") (class "Default")
      (node (ref "DD1") (pin "F22") (pinfunction "IO_L23N_T3_35_F22") (pintype "passive"))
    )
    (net (code "56") (name "/ADC1_D11_P") (class "Default")
      (node (ref "DD1") (pin "F21") (pinfunction "IO_L23P_T3_35_F21") (pintype "passive"))
    )
    (net (code "57") (name "/ADC1_D12_N") (class "Default")
      (node (ref "DD1") (pin "C20") (pinfunction "IO_L14N_T2_AD4N_SRCC_35_C20") (pintype "passive"))
    )
    (net (code "58") (name "/ADC1_D12_P") (class "Default")
      (node (ref "DD1") (pin "D20") (pinfunction "IO_L14P_T2_AD4P_SRCC_35_D20") (pintype "passive"))
    )
    (net (code "59") (name "/ADC1_D13_N") (class "Default")
      (node (ref "DD1") (pin "G22") (pinfunction "IO_L24N_T3_AD15N_35_G22") (pintype "passive"))
    )
    (net (code "60") (name "/ADC1_D13_P") (class "Default")
      (node (ref "DD1") (pin "H22") (pinfunction "IO_L24P_T3_AD15P_35_H22") (pintype "passive"))
    )
    (net (code "61") (name "/ADC1_D14_N") (class "Default")
      (node (ref "DD1") (pin "E20") (pinfunction "IO_L21N_T3_DQS_AD14N_35_E20") (pintype "passive"))
    )
    (net (code "62") (name "/ADC1_D14_P") (class "Default")
      (node (ref "DD1") (pin "E19") (pinfunction "IO_L21P_T3_DQS_AD14P_35_E19") (pintype "passive"))
    )
    (net (code "63") (name "/ADC1_D15_N") (class "Default")
      (node (ref "DD1") (pin "E18") (pinfunction "IO_L5N_T0_AD9N_35_E18") (pintype "passive"))
    )
    (net (code "64") (name "/ADC1_D15_P") (class "Default")
      (node (ref "DD1") (pin "F18") (pinfunction "IO_L5P_T0_AD9P_35_F18") (pintype "passive"))
    )
    (net (code "65") (name "/CAT_DTR") (class "Default")
      (node (ref "DD1") (pin "W8") (pinfunction "IO_L2N_T0_13_W8") (pintype "passive"))
    )
    (net (code "66") (name "/CAT_RTS") (class "Default")
      (node (ref "DD1") (pin "U10") (pinfunction "IO_L6P_T0_13_U10") (pintype "passive"))
    )
    (net (code "67") (name "/CLKOUT0_N") (class "Default")
      (node (ref "DD1") (pin "M20") (pinfunction "IO_L13N_T2_MRCC_34_M20") (pintype "passive"))
    )
    (net (code "68") (name "/CLKOUT0_P") (class "Default")
      (node (ref "DD1") (pin "M19") (pinfunction "IO_L13P_T2_MRCC_34_M19") (pintype "passive"))
    )
    (net (code "69") (name "/CLKOUT1_N") (class "Default")
      (node (ref "DD1") (pin "B20") (pinfunction "IO_L13N_T2_MRCC_35_B20") (pintype "passive"))
    )
    (net (code "70") (name "/CLKOUT1_P") (class "Default")
      (node (ref "DD1") (pin "B19") (pinfunction "IO_L13P_T2_MRCC_35_B19") (pintype "passive"))
    )
    (net (code "71") (name "/CW_KEY") (class "Default")
      (node (ref "DD1") (pin "V8") (pinfunction "IO_L2P_T0_13_V8") (pintype "passive"))
    )
    (net (code "72") (name "/DAC_D0_N") (class "Default")
      (node (ref "DD1") (pin "V19") (pinfunction "IO_L6N_T0_VREF_33_V19") (pintype "passive"))
    )
    (net (code "73") (name "/DAC_D0_P") (class "Default")
      (node (ref "DD1") (pin "V18") (pinfunction "IO_L6P_T0_33_V18") (pintype "passive"))
    )
    (net (code "74") (name "/DAC_D1_N") (class "Default")
      (node (ref "DD1") (pin "AA14") (pinfunction "IO_L22N_T3_33_AA14") (pintype "passive"))
    )
    (net (code "75") (name "/DAC_D1_P") (class "Default")
      (node (ref "DD1") (pin "Y14") (pinfunction "IO_L22P_T3_33_Y14") (pintype "passive"))
    )
    (net (code "76") (name "/DAC_D2_N") (class "Default")
      (node (ref "DD1") (pin "U16") (pinfunction "IO_L15N_T2_DQS_33_U16") (pintype "passive"))
    )
    (net (code "77") (name "/DAC_D2_P") (class "Default")
      (node (ref "DD1") (pin "U15") (pinfunction "IO_L15P_T2_DQS_33_U15") (pintype "passive"))
    )
    (net (code "78") (name "/DAC_D3_N") (class "Default")
      (node (ref "DD1") (pin "W21") (pinfunction "IO_L4N_T0_33_W21") (pintype "passive"))
    )
    (net (code "79") (name "/DAC_D3_P") (class "Default")
      (node (ref "DD1") (pin "W20") (pinfunction "IO_L4P_T0_33_W20") (pintype "passive"))
    )
    (net (code "80") (name "/DAC_D4_N") (class "Default")
      (node (ref "DD1") (pin "AA13") (pinfunction "IO_L23N_T3_33_AA13") (pintype "passive"))
    )
    (net (code "81") (name "/DAC_D4_P") (class "Default")
      (node (ref "DD1") (pin "Y13") (pinfunction "IO_L23P_T3_33_Y13") (pintype "passive"))
    )
    (net (code "82") (name "/DAC_D5_N") (class "Default")
      (node (ref "DD1") (pin "V17") (pinfunction "IO_L16N_T2_33_V17") (pintype "passive"))
    )
    (net (code "83") (name "/DAC_D5_P") (class "Default")
      (node (ref "DD1") (pin "U17") (pinfunction "IO_L16P_T2_33_U17") (pintype "passive"))
    )
    (net (code "84") (name "/DAC_D6_N") (class "Default")
      (node (ref "DD1") (pin "AB15") (pinfunction "IO_L24N_T3_33_AB15") (pintype "passive"))
    )
    (net (code "85") (name "/DAC_D6_P") (class "Default")
      (node (ref "DD1") (pin "AB14") (pinfunction "IO_L24P_T3_33_AB14") (pintype "passive"))
    )
    (net (code "86") (name "/DAC_D7_N") (class "Default")
      (node (ref "DD1") (pin "AB16") (pinfunction "IO_L18N_T2_33_AB16") (pintype "passive"))
    )
    (net (code "87") (name "/DAC_D7_P") (class "Default")
      (node (ref "DD1") (pin "AA16") (pinfunction "IO_L18P_T2_33_AA16") (pintype "passive"))
    )
    (net (code "88") (name "/DAC_D8_N") (class "Default")
      (node (ref "DD1") (pin "AB17") (pinfunction "IO_L17N_T2_33_AB17") (pintype "passive"))
    )
    (net (code "89") (name "/DAC_D8_P") (class "Default")
      (node (ref "DD1") (pin "AA17") (pinfunction "IO_L17P_T2_33_AA17") (pintype "passive"))
    )
    (net (code "90") (name "/DAC_D9_N") (class "Default")
      (node (ref "DD1") (pin "AB20") (pinfunction "IO_L10N_T1_33_AB20") (pintype "passive"))
    )
    (net (code "91") (name "/DAC_D9_P") (class "Default")
      (node (ref "DD1") (pin "AB19") (pinfunction "IO_L10P_T1_33_AB19") (pintype "passive"))
    )
    (net (code "92") (name "/DAC_D10_N") (class "Default")
      (node (ref "DD1") (pin "AB21") (pinfunction "IO_L8N_T1_33_AB21") (pintype "passive"))
    )
    (net (code "93") (name "/DAC_D10_P") (class "Default")
      (node (ref "DD1") (pin "AA21") (pinfunction "IO_L8P_T1_33_AA21") (pintype "passive"))
    )
    (net (code "94") (name "/DAC_D11_N") (class "Default")
      (node (ref "DD1") (pin "V20") (pinfunction "IO_L5N_T0_33_V20") (pintype "passive"))
    )
    (net (code "95") (name "/DAC_D11_P") (class "Default")
      (node (ref "DD1") (pin "U20") (pinfunction "IO_L5P_T0_33_U20") (pintype "passive"))
    )
    (net (code "96") (name "/DAC_D12_N") (class "Default")
      (node (ref "DD1") (pin "U21") (pinfunction "IO_L1N_T0_33_U21") (pintype "passive"))
    )
    (net (code "97") (name "/DAC_D12_P") (class "Default")
      (node (ref "DD1") (pin "T21") (pinfunction "IO_L1P_T0_33_T21") (pintype "passive"))
    )
    (net (code "98") (name "/DAC_D13_N") (class "Default")
      (node (ref "DD1") (pin "AB22") (pinfunction "IO_L7N_T1_33_AB22") (pintype "passive"))
    )
    (net (code "99") (name "/DAC_D13_P") (class "Default")
      (node (ref "DD1") (pin "AA22") (pinfunction "IO_L7P_T1_33_AA22") (pintype "passive"))
    )
    (net (code "100") (name "/DAC_D14_N") (class "Default")
      (node (ref "DD1") (pin "W22") (pinfunction "IO_L3N_T0_DQS_33_W22") (pintype "passive"))
    )
    (net (code "101") (name "/DAC_D14_P") (class "Default")
      (node (ref "DD1") (pin "V22") (pinfunction "IO_L3P_T0_DQS_33_V22") (pintype "passive"))
    )
    (net (code "102") (name "/DAC_D15_N") (class "Default")
      (node (ref "DD1") (pin "U22") (pinfunction "IO_L2N_T0_33_U22") (pintype "passive"))
    )
    (net (code "103") (name "/DAC_D15_P") (class "Default")
      (node (ref "DD1") (pin "T22") (pinfunction "IO_L2P_T0_33_T22") (pintype "passive"))
    )
    (net (code "104") (name "/DA_N") (class "Default")
      (node (ref "DA12") (pin "14") (pinfunction "MX4+_14") (pintype "passive"))
      (node (ref "XS1") (pin "2") (pinfunction "2_2") (pintype "passive"))
    )
    (net (code "105") (name "/DA_P") (class "Default")
      (node (ref "DA12") (pin "13") (pinfunction "MX4-_13") (pintype "passive"))
      (node (ref "XS1") (pin "1") (pinfunction "1_1") (pintype "passive"))
    )
    (net (code "106") (name "/DB_N") (class "Default")
      (node (ref "DA12") (pin "17") (pinfunction "MX3+_17") (pintype "passive"))
      (node (ref "XS1") (pin "4") (pinfunction "4_4") (pintype "passive"))
    )
    (net (code "107") (name "/DB_P") (class "Default")
      (node (ref "DA12") (pin "16") (pinfunction "MX3-_16") (pintype "passive"))
      (node (ref "XS1") (pin "3") (pinfunction "3_3") (pintype "passive"))
    )
    (net (code "108") (name "/DC_N") (class "Default")
      (node (ref "DA12") (pin "20") (pinfunction "MX2+_20") (pintype "passive"))
      (node (ref "XS1") (pin "6") (pinfunction "6_6") (pintype "passive"))
    )
    (net (code "109") (name "/DC_P") (class "Default")
      (node (ref "DA12") (pin "19") (pinfunction "MX2-_19") (pintype "passive"))
      (node (ref "XS1") (pin "5") (pinfunction "5_5") (pintype "passive"))
    )
    (net (code "110") (name "/DD_N") (class "Default")
      (node (ref "DA12") (pin "23") (pinfunction "MX1+_23") (pintype "passive"))
      (node (ref "XS1") (pin "8") (pinfunction "8_8") (pintype "passive"))
    )
    (net (code "111") (name "/DD_P") (class "Default")
      (node (ref "DA12") (pin "22") (pinfunction "MX1-_22") (pintype "passive"))
      (node (ref "XS1") (pin "7") (pinfunction "7_7") (pintype "passive"))
    )
    (net (code "112") (name "/DIS_RS422_RX") (class "Default")
      (node (ref "DD1") (pin "AA6") (pinfunction "IO_L14N_T2_SRCC_13_AA6") (pintype "passive"))
    )
    (net (code "113") (name "/DIS_RS422_TX") (class "Default")
      (node (ref "DD1") (pin "AB4") (pinfunction "IO_L16N_T2_13_AB4") (pintype "passive"))
    )
    (net (code "114") (name "/ETH0_LEDGRN") (class "Default")
      (node (ref "DD7") (pin "17") (pinfunction "LED1/PME_N1/PHYAD0_17") (pintype "bidirectional"))
      (node (ref "R81") (pin "2") (pinfunction "2_2") (pintype "passive"))
    )
    (net (code "115") (name "/ETH0_LEDYEL") (class "Default")
      (node (ref "DD7") (pin "15") (pinfunction "LED2/PHYAD1_15") (pintype "bidirectional"))
      (node (ref "R83") (pin "2") (pinfunction "2_2") (pintype "passive"))
    )
    (net (code "116") (name "/ETH0_TD0_N") (class "Default")
      (node (ref "DA12") (pin "11") (pinfunction "TD4+_11") (pintype "passive"))
      (node (ref "DD7") (pin "3") (pinfunction "TXRXM_A_3") (pintype "bidirectional"))
    )
    (net (code "117") (name "/ETH0_TD0_P") (class "Default")
      (node (ref "DA12") (pin "12") (pinfunction "TD4-_12") (pintype "passive"))
      (node (ref "DD7") (pin "2") (pinfunction "TXRXP_A_2") (pintype "bidirectional"))
    )
    (net (code "118") (name "/ETH0_TD1_N") (class "Default")
      (node (ref "DA12") (pin "8") (pinfunction "TD3+_8") (pintype "passive"))
      (node (ref "DD7") (pin "6") (pinfunction "TXRXM_B_6") (pintype "bidirectional"))
    )
    (net (code "119") (name "/ETH0_TD1_P") (class "Default")
      (node (ref "DA12") (pin "9") (pinfunction "TD3-_9") (pintype "passive"))
      (node (ref "DD7") (pin "5") (pinfunction "TXRXP_B_5") (pintype "bidirectional"))
    )
    (net (code "120") (name "/ETH0_TD2_N") (class "Default")
      (node (ref "DA12") (pin "5") (pinfunction "TD2+_5") (pintype "passive"))
      (node (ref "DD7") (pin "8") (pinfunction "TXRXM_C_8") (pintype "bidirectional"))
    )
    (net (code "121") (name "/ETH0_TD2_P") (class "Default")
      (node (ref "DA12") (pin "6") (pinfunction "TD2-_6") (pintype "passive"))
      (node (ref "DD7") (pin "7") (pinfunction "TXRXP_C_7") (pintype "bidirectional"))
    )
    (net (code "122") (name "/ETH0_TD3_N") (class "Default")
      (node (ref "DA12") (pin "2") (pinfunction "TD1+_2") (pintype "passive"))
      (node (ref "DD7") (pin "11") (pinfunction "TXRXM_D_11") (pintype "bidirectional"))
    )
    (net (code "123") (name "/ETH0_TD3_P") (class "Default")
      (node (ref "DA12") (pin "3") (pinfunction "TD1-_3") (pintype "passive"))
      (node (ref "DD7") (pin "10") (pinfunction "TXRXP_D_10") (pintype "bidirectional"))
    )
    (net (code "124") (name "/ETH_INT") (class "Default")
      (node (ref "DD1") (pin "AB1") (pinfunction "IO_L15N_T2_DQS_13_AB1") (pintype "passive"))
      (node (ref "DD7") (pin "38") (pinfunction "INT_N/PME_N2_38") (pintype "output"))
    )
    (net (code "125") (name "/ETH_MDC") (class "Default")
      (node (ref "DD1") (pin "AB2") (pinfunction "IO_L15P_T2_DQS_13_AB2") (pintype "passive"))
      (node (ref "DD7") (pin "36") (pinfunction "MDC_36") (pintype "input"))
      (node (ref "R79") (pin "1") (pinfunction "1_1") (pintype "passive"))
    )
    (net (code "126") (name "/ETH_MDIO") (class "Default")
      (node (ref "DD1") (pin "Y4") (pinfunction "IO_L18P_T2_13_Y4") (pintype "passive"))
      (node (ref "DD7") (pin "37") (pinfunction "MDIO_37") (pintype "bidirectional"))
      (node (ref "R78") (pin "1") (pinfunction "1_1") (pintype "passive"))
    )
    (net (code "127") (name "/ETH_RST") (class "Default")
      (node (ref "C155") (pin "2") (pinfunction "2_2") (pintype "passive"))
      (node (ref "DD1") (pin "U11") (pinfunction "IO_L5N_T0_13_U11") (pintype "passive"))
      (node (ref "DD7") (pin "42") (pinfunction "RESET_N_42") (pintype "input"))
      (node (ref "R70") (pin "1") (pinfunction "1_1") (pintype "passive"))
    )
    (net (code "128") (name "/ETH_RXC") (class "Default")
      (node (ref "DD7") (pin "35") (pinfunction "RX_CLK/PHYAD2_35") (pintype "bidirectional"))
      (node (ref "R60") (pin "1") (pinfunction "1_1") (pintype "passive"))
      (node (ref "R75") (pin "1") (pinfunction "1_1") (pintype "passive"))
    )
    (net (code "129") (name "/ETH_RXCTL") (class "Default")
      (node (ref "DD7") (pin "33") (pinfunction "RX_DV/CLK125_EN_33") (pintype "bidirectional"))
      (node (ref "R65") (pin "1") (pinfunction "1_1") (pintype "passive"))
      (node (ref "R76") (pin "1") (pinfunction "1_1") (pintype "passive"))
    )
    (net (code "130") (name "/ETH_RXD0") (class "Default")
      (node (ref "DD7") (pin "32") (pinfunction "RXD0/MODE0_32") (pintype "bidirectional"))
      (node (ref "R66") (pin "2") (pinfunction "2_2") (pintype "passive"))
      (node (ref "R71") (pin "1") (pinfunction "1_1") (pintype "passive"))
    )
    (net (code "131") (name "/ETH_RXD1") (class "Default")
      (node (ref "DD7") (pin "31") (pinfunction "RXD1/MODE1_31") (pintype "bidirectional"))
      (node (ref "R67") (pin "2") (pinfunction "2_2") (pintype "passive"))
      (node (ref "R72") (pin "1") (pinfunction "1_1") (pintype "passive"))
    )
    (net (code "132") (name "/ETH_RXD2") (class "Default")
      (node (ref "DD7") (pin "28") (pinfunction "RXD2/MODE2_28") (pintype "bidirectional"))
      (node (ref "R68") (pin "1") (pinfunction "1_1") (pintype "passive"))
      (node (ref "R73") (pin "1") (pinfunction "1_1") (pintype "passive"))
    )
    (net (code "133") (name "/ETH_RXD3") (class "Default")
      (node (ref "DD7") (pin "27") (pinfunction "RXD3/MODE3_27") (pintype "bidirectional"))
      (node (ref "R69") (pin "1") (pinfunction "1_1") (pintype "passive"))
      (node (ref "R74") (pin "1") (pinfunction "1_1") (pintype "passive"))
    )
    (net (code "134") (name "/ETH_TXC") (class "Default")
      (node (ref "DD1") (pin "AA11") (pinfunction "IO_L8P_T1_13_AA11") (pintype "passive"))
      (node (ref "DD7") (pin "24") (pinfunction "GTX_CLK_24") (pintype "input"))
    )
    (net (code "135") (name "/ETH_TXCTL") (class "Default")
      (node (ref "DD1") (pin "AB10") (pinfunction "IO_L9P_T1_DQS_13_AB10") (pintype "passive"))
      (node (ref "DD7") (pin "25") (pinfunction "TX_EN_25") (pintype "input"))
    )
    (net (code "136") (name "/ETH_TXD0") (class "Default")
      (node (ref "DD1") (pin "Y5") (pinfunction "IO_L13N_T2_MRCC_13_Y5") (pintype "passive"))
      (node (ref "DD7") (pin "19") (pinfunction "TXD0_19") (pintype "input"))
    )
    (net (code "137") (name "/ETH_TXD1") (class "Default")
      (node (ref "DD1") (pin "AA12") (pinfunction "IO_L7P_T1_13_AA12") (pintype "passive"))
      (node (ref "DD7") (pin "20") (pinfunction "TXD1_20") (pintype "input"))
    )
    (net (code "138") (name "/ETH_TXD2") (class "Default")
      (node (ref "DD1") (pin "AB12") (pinfunction "IO_L7N_T1_13_AB12") (pintype "passive"))
      (node (ref "DD7") (pin "21") (pinfunction "TXD2_21") (pintype "input"))
    )
    (net (code "139") (name "/ETH_TXD3") (class "Default")
      (node (ref "DD1") (pin "AB11") (pinfunction "IO_L8N_T1_13_AB11") (pintype "passive"))
      (node (ref "DD7") (pin "22") (pinfunction "TXD3_22") (pintype "input"))
    )
    (net (code "140") (name "/I2S1BCLK") (class "Default")
      (node (ref "DD1") (pin "AA4") (pinfunction "IO_L18N_T2_13_AA4") (pintype "passive"))
    )
    (net (code "141") (name "/I2S1DATA0") (class "Default")
      (node (ref "DD1") (pin "W6") (pinfunction "IO_L24P_T3_13_W6") (pintype "passive"))
    )
    (net (code "142") (name "/I2S1DATA1") (class "Default")
      (node (ref "DD1") (pin "W5") (pinfunction "IO_L24N_T3_13_W5") (pintype "passive"))
    )
    (net (code "143") (name "/I2S1MCLK") (class "Default")
      (node (ref "DD1") (pin "Y9") (pinfunction "IO_L12P_T1_MRCC_13_Y9") (pintype "passive"))
    )
    (net (code "144") (name "/I2S1WCLK") (class "Default")
      (node (ref "DD1") (pin "Y6") (pinfunction "IO_L13P_T2_MRCC_13_Y6") (pintype "passive"))
    )
    (net (code "145") (name "/PTT") (class "Default")
      (node (ref "DD1") (pin "V9") (pinfunction "IO_L1N_T0_13_V9") (pintype "passive"))
    )
    (net (code "146") (name "/PUDC_B") (class "Default")
      (node (ref "DD1") (pin "K16") (pinfunction "IO_L3P_T0_DQS_PUDC_B_34_K16") (pintype "passive"))
      (node (ref "R61") (pin "1") (pinfunction "1_1") (pintype "passive"))
    )
    (net (code "147") (name "/RS422_RX") (class "Default")
      (node (ref "DD1") (pin "Y8") (pinfunction "IO_L12N_T1_MRCC_13_Y8") (pintype "passive"))
    )
    (net (code "148") (name "/RS422_TX") (class "Default")
      (node (ref "DD1") (pin "W7") (pinfunction "IO_L23N_T3_13_W7") (pintype "passive"))
    )
    (net (code "149") (name "/SERCLK_N") (class "Default")
      (node (ref "DD1") (pin "T18") (pinfunction "IO_L23N_T3_34_T18") (pintype "passive"))
      (node (ref "XS4") (pin "5") (pinfunction "5_5") (pintype "passive"))
    )
    (net (code "150") (name "/SERCLK_P") (class "Default")
      (node (ref "DD1") (pin "R18") (pinfunction "IO_L23P_T3_34_R18") (pintype "passive"))
      (node (ref "XS4") (pin "6") (pinfunction "6_6") (pintype "passive"))
    )
    (net (code "151") (name "/SERDATA_N") (class "Default")
      (node (ref "DD1") (pin "W13") (pinfunction "IO_L20N_T3_33_W13") (pintype "passive"))
      (node (ref "XS4") (pin "3") (pinfunction "3_3") (pintype "passive"))
    )
    (net (code "152") (name "/SERDATA_P") (class "Default")
      (node (ref "DD1") (pin "V13") (pinfunction "IO_L20P_T3_33_V13") (pintype "passive"))
      (node (ref "XS4") (pin "2") (pinfunction "2_2") (pintype "passive"))
    )
    (net (code "153") (name "/TX_FAIL") (class "Default")
      (node (ref "DD1") (pin "V7") (pinfunction "IO_L23P_T3_13_V7") (pintype "passive"))
    )
    (net (code "154") (name "/TX_ON") (class "Default")
      (node (ref "DD1") (pin "V5") (pinfunction "IO_L21P_T3_DQS_13_V5") (pintype "passive"))
    )
    (net (code "155") (name "DAC_DCI_N") (class "Default")
      (node (ref "DD1") (pin "Y16") (pinfunction "IO_L14N_T2_SRCC_33_Y16") (pintype "passive"))
    )
    (net (code "156") (name "DAC_DCI_P") (class "Default")
      (node (ref "DD1") (pin "W16") (pinfunction "IO_L14P_T2_SRCC_33_W16") (pintype "passive"))
    )
    (net (code "157") (name "DAC_DCO_N") (class "Default")
      (node (ref "DD1") (pin "AA19") (pinfunction "IO_L11N_T1_SRCC_33_AA19") (pintype "passive"))
    )
    (net (code "158") (name "DAC_DCO_P") (class "Default")
      (node (ref "DD1") (pin "Y19") (pinfunction "IO_L11P_T1_SRCC_33_Y19") (pintype "passive"))
    )
    (net (code "159") (name "ETH0_1V2") (class "Default")
      (node (ref "C131") (pin "2") (pinfunction "2_2") (pintype "passive"))
      (node (ref "L16") (pin "2") (pinfunction "2_2") (pintype "passive"))
      (node (ref "L19") (pin "1") (pinfunction "1_1") (pintype "passive"))
      (node (ref "L20") (pin "1") (pinfunction "1_1") (pintype "passive"))
      (node (ref "L21") (pin "1") (pinfunction "1_1") (pintype "passive"))
      (node (ref "R63") (pin "2") (pinfunction "2_2") (pintype "passive"))
    )
    (net (code "160") (name "ETH0_3V3") (class "Default")
      (node (ref "C146") (pin "2") (pinfunction "2_2") (pintype "passive"))
      (node (ref "DA11") (pin "7") (pinfunction "EN_7") (pintype "input"))
      (node (ref "L17") (pin "2") (pinfunction "2_2") (pintype "passive"))
      (node (ref "L18") (pin "1") (pinfunction "1_1") (pintype "passive"))
      (node (ref "R62") (pin "2") (pinfunction "2_2") (pintype "passive"))
      (node (ref "R71") (pin "2") (pinfunction "2_2") (pintype "passive"))
      (node (ref "R72") (pin "2") (pinfunction "2_2") (pintype "passive"))
      (node (ref "R73") (pin "2") (pinfunction "2_2") (pintype "passive"))
      (node (ref "R74") (pin "2") (pinfunction "2_2") (pintype "passive"))
      (node (ref "R75") (pin "2") (pinfunction "2_2") (pintype "passive"))
      (node (ref "R77") (pin "2") (pinfunction "2_2") (pintype "passive"))
      (node (ref "R78") (pin "2") (pinfunction "2_2") (pintype "passive"))
      (node (ref "R79") (pin "2") (pinfunction "2_2") (pintype "passive"))
      (node (ref "R81") (pin "1") (pinfunction "1_1") (pintype "passive"))
      (node (ref "R83") (pin "1") (pinfunction "1_1") (pintype "passive"))
    )
    (net (code "161") (name "GND") (class "Default")
      (node (ref "C128") (pin "1") (pinfunction "1_1") (pintype "passive"))
      (node (ref "C129") (pin "1") (pinfunction "1_1") (pintype "passive"))
      (node (ref "C131") (pin "1") (pinfunction "1_1") (pintype "passive"))
      (node (ref "C132") (pin "1") (pinfunction "1_1") (pintype "passive"))
      (node (ref "C133") (pin "1") (pinfunction "1_1") (pintype "passive"))
      (node (ref "C134") (pin "1") (pinfunction "1_1") (pintype "passive"))
      (node (ref "C135") (pin "1") (pinfunction "1_1") (pintype "passive"))
      (node (ref "C136") (pin "1") (pinfunction "1_1") (pintype "passive"))
      (node (ref "C138") (pin "1") (pinfunction "1_1") (pintype "passive"))
      (node (ref "C139") (pin "1") (pinfunction "1_1") (pintype "passive"))
      (node (ref "C140") (pin "1") (pinfunction "1_1") (pintype "passive"))
      (node (ref "C142") (pin "1") (pinfunction "1_1") (pintype "passive"))
      (node (ref "C143") (pin "1") (pinfunction "1_1") (pintype "passive"))
      (node (ref "C144") (pin "1") (pinfunction "1_1") (pintype "passive"))
      (node (ref "C145") (pin "1") (pinfunction "1_1") (pintype "passive"))
      (node (ref "C146") (pin "1") (pinfunction "1_1") (pintype "passive"))
      (node (ref "C147") (pin "1") (pinfunction "1_1") (pintype "passive"))
      (node (ref "C148") (pin "1") (pinfunction "1_1") (pintype "passive"))
      (node (ref "C149") (pin "1") (pinfunction "1_1") (pintype "passive"))
      (node (ref "C150") (pin "1") (pinfunction "1_1") (pintype "passive"))
      (node (ref "C151") (pin "1") (pinfunction "1_1") (pintype "passive"))
      (node (ref "C152") (pin "1") (pinfunction "1_1") (pintype "passive"))
      (node (ref "C153") (pin "1") (pinfunction "1_1") (pintype "passive"))
      (node (ref "C154") (pin "1") (pinfunction "1_1") (pintype "passive"))
      (node (ref "C155") (pin "1") (pinfunction "1_1") (pintype "passive"))
      (node (ref "C156") (pin "1") (pinfunction "1_1") (pintype "passive"))
      (node (ref "C157") (pin "1") (pinfunction "1_1") (pintype "passive"))
      (node (ref "C158") (pin "1") (pinfunction "1_1") (pintype "passive"))
      (node (ref "C159") (pin "1") (pinfunction "1_1") (pintype "passive"))
      (node (ref "C160") (pin "1") (pinfunction "1_1") (pintype "passive"))
      (node (ref "C161") (pin "1") (pinfunction "1_1") (pintype "passive"))
      (node (ref "C162") (pin "1") (pinfunction "1_1") (pintype "passive"))
      (node (ref "C163") (pin "1") (pinfunction "1_1") (pintype "passive"))
      (node (ref "C164") (pin "1") (pinfunction "1_1") (pintype "passive"))
      (node (ref "C165") (pin "1") (pinfunction "1_1") (pintype "passive"))
      (node (ref "C166") (pin "1") (pinfunction "1_1") (pintype "passive"))
      (node (ref "C167") (pin "1") (pinfunction "1_1") (pintype "passive"))
      (node (ref "C168") (pin "1") (pinfunction "1_1") (pintype "passive"))
      (node (ref "C169") (pin "1") (pinfunction "1_1") (pintype "passive"))
      (node (ref "C170") (pin "1") (pinfunction "1_1") (pintype "passive"))
      (node (ref "C171") (pin "1") (pinfunction "1_1") (pintype "passive"))
      (node (ref "C172") (pin "1") (pinfunction "1_1") (pintype "passive"))
      (node (ref "C173") (pin "2") (pinfunction "2_2") (pintype "passive"))
      (node (ref "C174") (pin "1") (pinfunction "1_1") (pintype "passive"))
      (node (ref "C175") (pin "1") (pinfunction "1_1") (pintype "passive"))
      (node (ref "C176") (pin "1") (pinfunction "1_1") (pintype "passive"))
      (node (ref "C177") (pin "1") (pinfunction "1_1") (pintype "passive"))
      (node (ref "C178") (pin "1") (pinfunction "1_1") (pintype "passive"))
      (node (ref "C179") (pin "1") (pinfunction "1_1") (pintype "passive"))
      (node (ref "C180") (pin "1") (pinfunction "1_1") (pintype "passive"))
      (node (ref "C181") (pin "2") (pinfunction "2_2") (pintype "passive"))
      (node (ref "DA11") (pin "1") (pinfunction "GND_1") (pintype "passive"))
      (node (ref "DD7") (pin "29") (pinfunction "VSS_29") (pintype "passive"))
      (node (ref "DD7") (pin "49") (pinfunction "P_GND_49") (pintype "passive"))
      (node (ref "R64") (pin "2") (pinfunction "2_2") (pintype "passive"))
      (node (ref "R76") (pin "2") (pinfunction "2_2") (pintype "passive"))
      (node (ref "R80") (pin "2") (pinfunction "2_2") (pintype "passive"))
      (node (ref "R87") (pin "2") (pinfunction "2_2") (pintype "passive"))
      (node (ref "XS4") (pin "1") (pinfunction "1_1") (pintype "passive"))
      (node (ref "XS4") (pin "4") (pinfunction "4_4") (pintype "passive"))
      (node (ref "XS4") (pin "7") (pinfunction "7_7") (pintype "passive"))
    )
    (net (code "162") (name "Net-(BQ1-OSC1)") (class "Default")
      (node (ref "BQ1") (pin "1") (pinfunction "OSC1_1") (pintype "passive"))
      (node (ref "C175") (pin "2") (pinfunction "2_2") (pintype "passive"))
      (node (ref "DD7") (pin "46") (pinfunction "XI_46") (pintype "input"))
    )
    (net (code "163") (name "Net-(BQ1-OSC2)") (class "Default")
      (node (ref "BQ1") (pin "3") (pinfunction "OSC2_3") (pintype "passive"))
      (node (ref "C176") (pin "2") (pinfunction "2_2") (pintype "passive"))
      (node (ref "DD7") (pin "45") (pinfunction "XO_45") (pintype "output"))
    )
    (net (code "164") (name "Net-(C166-Pad2)") (class "Default")
      (node (ref "C166") (pin "2") (pinfunction "2_2") (pintype "passive"))
      (node (ref "C167") (pin "2") (pinfunction "2_2") (pintype "passive"))
      (node (ref "C168") (pin "2") (pinfunction "2_2") (pintype "passive"))
      (node (ref "C170") (pin "2") (pinfunction "2_2") (pintype "passive"))
      (node (ref "DD7") (pin "1") (pinfunction "AVDDH_1") (pintype "power_in"))
      (node (ref "DD7") (pin "12") (pinfunction "AVDDH_12") (pintype "power_in"))
      (node (ref "DD7") (pin "16") (pinfunction "DVDDH_16") (pintype "power_in"))
      (node (ref "DD7") (pin "34") (pinfunction "DVDDH_34") (pintype "power_in"))
      (node (ref "DD7") (pin "40") (pinfunction "DVDDH_40") (pintype "power_in"))
      (node (ref "L18") (pin "2") (pinfunction "2_2") (pintype "passive"))
    )
    (net (code "165") (name "Net-(C169-Pad2)") (class "Default")
      (node (ref "C169") (pin "2") (pinfunction "2_2") (pintype "passive"))
      (node (ref "C171") (pin "2") (pinfunction "2_2") (pintype "passive"))
      (node (ref "C172") (pin "2") (pinfunction "2_2") (pintype "passive"))
      (node (ref "C177") (pin "2") (pinfunction "2_2") (pintype "passive"))
      (node (ref "DD7") (pin "14") (pinfunction "DVDDL_14") (pintype "power_in"))
      (node (ref "DD7") (pin "18") (pinfunction "DVDDL_18") (pintype "power_in"))
      (node (ref "DD7") (pin "23") (pinfunction "DVDDL_23") (pintype "power_in"))
      (node (ref "DD7") (pin "26") (pinfunction "DVDDL_26") (pintype "power_in"))
      (node (ref "DD7") (pin "30") (pinfunction "DVDDL_30") (pintype "power_in"))
      (node (ref "DD7") (pin "39") (pinfunction "DVDDL_39") (pintype "power_in"))
      (node (ref "L19") (pin "2") (pinfunction "2_2") (pintype "passive"))
    )
    (net (code "166") (name "Net-(C173-Pad1)") (class "Default")
      (node (ref "C173") (pin "1") (pinfunction "1_1") (pintype "passive"))
      (node (ref "R82") (pin "2") (pinfunction "2_2") (pintype "passive"))
      (node (ref "R84") (pin "2") (pinfunction "2_2") (pintype "passive"))
      (node (ref "R85") (pin "2") (pinfunction "2_2") (pintype "passive"))
      (node (ref "R86") (pin "2") (pinfunction "2_2") (pintype "passive"))
    )
    (net (code "167") (name "Net-(C174-Pad2)") (class "Default")
      (node (ref "C174") (pin "2") (pinfunction "2_2") (pintype "passive"))
      (node (ref "C179") (pin "2") (pinfunction "2_2") (pintype "passive"))
      (node (ref "DD7") (pin "4") (pinfunction "AVDDL_4") (pintype "power_in"))
      (node (ref "DD7") (pin "9") (pinfunction "AVDDL_9") (pintype "power_in"))
      (node (ref "L20") (pin "2") (pinfunction "2_2") (pintype "passive"))
    )
    (net (code "168") (name "Net-(C181-Pad1)") (class "Default")
      (node (ref "C181") (pin "1") (pinfunction "1_1") (pintype "passive"))
      (node (ref "R87") (pin "1") (pinfunction "1_1") (pintype "passive"))
      (node (ref "XS1") (pin "9") (pinfunction "9_9") (pintype "passive"))
    )
    (net (code "169") (name "Net-(DA11-SS)") (class "Default")
      (node (ref "C129") (pin "2") (pinfunction "2_2") (pintype "passive"))
      (node (ref "DA11") (pin "5") (pinfunction "SS_5") (pintype "passive"))
    )
    (net (code "170") (name "Net-(DA11-SW)") (class "Default")
      (node (ref "C130") (pin "1") (pinfunction "1_1") (pintype "passive"))
      (node (ref "DA11") (pin "2") (pinfunction "SW_2") (pintype "passive"))
      (node (ref "L16") (pin "1") (pinfunction "1_1") (pintype "passive"))
    )
    (net (code "171") (name "Net-(DA11-VBST)") (class "Default")
      (node (ref "C130") (pin "2") (pinfunction "2_2") (pintype "passive"))
      (node (ref "DA11") (pin "8") (pinfunction "VBST_8") (pintype "passive"))
    )
    (net (code "172") (name "Net-(DA11-VFB)") (class "Default")
      (node (ref "DA11") (pin "6") (pinfunction "VFB_6") (pintype "passive"))
      (node (ref "R63") (pin "1") (pinfunction "1_1") (pintype "passive"))
      (node (ref "R64") (pin "1") (pinfunction "1_1") (pintype "passive"))
    )
    (net (code "173") (name "Net-(DA12-MCT1)") (class "Default")
      (node (ref "DA12") (pin "24") (pinfunction "MCT1_24") (pintype "passive"))
      (node (ref "R86") (pin "1") (pinfunction "1_1") (pintype "passive"))
    )
    (net (code "174") (name "Net-(DA12-MCT2)") (class "Default")
      (node (ref "DA12") (pin "21") (pinfunction "MCT2_21") (pintype "passive"))
      (node (ref "R85") (pin "1") (pinfunction "1_1") (pintype "passive"))
    )
    (net (code "175") (name "Net-(DA12-MCT3)") (class "Default")
      (node (ref "DA12") (pin "18") (pinfunction "MCT3_18") (pintype "passive"))
      (node (ref "R84") (pin "1") (pinfunction "1_1") (pintype "passive"))
    )
    (net (code "176") (name "Net-(DA12-MCT4)") (class "Default")
      (node (ref "DA12") (pin "15") (pinfunction "MCT4_15") (pintype "passive"))
      (node (ref "R82") (pin "1") (pinfunction "1_1") (pintype "passive"))
    )
    (net (code "177") (name "Net-(DA12-TCT1)") (class "Default")
      (node (ref "C162") (pin "2") (pinfunction "2_2") (pintype "passive"))
      (node (ref "DA12") (pin "1") (pinfunction "TCT1_1") (pintype "passive"))
    )
    (net (code "178") (name "Net-(DA12-TCT2)") (class "Default")
      (node (ref "C163") (pin "2") (pinfunction "2_2") (pintype "passive"))
      (node (ref "DA12") (pin "4") (pinfunction "TCT2_4") (pintype "passive"))
    )
    (net (code "179") (name "Net-(DA12-TCT3)") (class "Default")
      (node (ref "C164") (pin "2") (pinfunction "2_2") (pintype "passive"))
      (node (ref "DA12") (pin "7") (pinfunction "TCT3_7") (pintype "passive"))
    )
    (net (code "180") (name "Net-(DA12-TCT4)") (class "Default")
      (node (ref "C165") (pin "2") (pinfunction "2_2") (pintype "passive"))
      (node (ref "DA12") (pin "10") (pinfunction "TCT4_10") (pintype "passive"))
    )
    (net (code "181") (name "Net-(DD1B-IO_L9N_T1_DQS_13)") (class "Default")
      (node (ref "DD1") (pin "AB9") (pinfunction "IO_L9N_T1_DQS_13_AB9") (pintype "passive"))
      (node (ref "R69") (pin "2") (pinfunction "2_2") (pintype "passive"))
    )
    (net (code "182") (name "Net-(DD1B-IO_L10P_T1_13)") (class "Default")
      (node (ref "DD1") (pin "Y11") (pinfunction "IO_L10P_T1_13_Y11") (pintype "passive"))
      (node (ref "R68") (pin "2") (pinfunction "2_2") (pintype "passive"))
    )
    (net (code "183") (name "Net-(DD1B-IO_L14P_T2_SRCC_13)") (class "Default")
      (node (ref "DD1") (pin "AA7") (pinfunction "IO_L14P_T2_SRCC_13_AA7") (pintype "passive"))
      (node (ref "R60") (pin "2") (pinfunction "2_2") (pintype "passive"))
    )
    (net (code "184") (name "Net-(DD1B-IO_L16P_T2_13)") (class "Default")
      (node (ref "DD1") (pin "AB5") (pinfunction "IO_L16P_T2_13_AB5") (pintype "passive"))
      (node (ref "R65") (pin "2") (pinfunction "2_2") (pintype "passive"))
    )
    (net (code "185") (name "Net-(DD1B-IO_L17N_T2_13)") (class "Default")
      (node (ref "DD1") (pin "AB6") (pinfunction "IO_L17N_T2_13_AB6") (pintype "passive"))
      (node (ref "R66") (pin "1") (pinfunction "1_1") (pintype "passive"))
    )
    (net (code "186") (name "Net-(DD1B-IO_L17P_T2_13)") (class "Default")
      (node (ref "DD1") (pin "AB7") (pinfunction "IO_L17P_T2_13_AB7") (pintype "passive"))
      (node (ref "R67") (pin "1") (pinfunction "1_1") (pintype "passive"))
    )
    (net (code "187") (name "Net-(DD1C-IO_L19P_T3_33)") (class "Default")
      (node (ref "DD1") (pin "V14") (pinfunction "IO_L19P_T3_33_V14") (pintype "passive"))
      (node (ref "X4") (pin "1") (pinfunction "~_1") (pintype "passive"))
    )
    (net (code "188") (name "Net-(DD1D-IO_L21P_T3_DQS_34)") (class "Default")
      (node (ref "DD1") (pin "T16") (pinfunction "IO_L21P_T3_DQS_34_T16") (pintype "passive"))
      (node (ref "X3") (pin "1") (pinfunction "~_1") (pintype "passive"))
    )
    (net (code "189") (name "Net-(DD7A-CLK125_NDO{slash}LED_MODE)") (class "Default")
      (node (ref "DD7") (pin "41") (pinfunction "CLK125_NDO/LED_MODE_41") (pintype "bidirectional"))
      (node (ref "R77") (pin "1") (pinfunction "1_1") (pintype "passive"))
    )
    (net (code "190") (name "Net-(DD7A-ISET)") (class "Default")
      (node (ref "DD7") (pin "48") (pinfunction "ISET_48") (pintype "bidirectional"))
      (node (ref "R80") (pin "1") (pinfunction "1_1") (pintype "passive"))
    )
    (net (code "191") (name "Net-(DD7B-AVDDL_PLL)") (class "Default")
      (node (ref "C178") (pin "2") (pinfunction "2_2") (pintype "passive"))
      (node (ref "C180") (pin "2") (pinfunction "2_2") (pintype "passive"))
      (node (ref "DD7") (pin "44") (pinfunction "AVDDL_PLL_44") (pintype "power_in"))
      (node (ref "L21") (pin "2") (pinfunction "2_2") (pintype "passive"))
    )
    (net (code "192") (name "PG_ETH0") (class "Default")
      (node (ref "DA11") (pin "4") (pinfunction "PG_4") (pintype "open_collector"))
      (node (ref "R62") (pin "1") (pinfunction "1_1") (pintype "passive"))
      (node (ref "R70") (pin "2") (pinfunction "2_2") (pintype "passive"))
    )
    (net (code "193") (name "VCC_5V0") (class "Default")
      (node (ref "C128") (pin "2") (pinfunction "2_2") (pintype "passive"))
      (node (ref "DA11") (pin "3") (pinfunction "VIN_3") (pintype "passive"))
    )
    (net (code "194") (name "VDD_2V5") (class "Default")
      (node (ref "C134") (pin "2") (pinfunction "2_2") (pintype "passive"))
      (node (ref "C135") (pin "2") (pinfunction "2_2") (pintype "passive"))
      (node (ref "C138") (pin "2") (pinfunction "2_2") (pintype "passive"))
      (node (ref "C139") (pin "2") (pinfunction "2_2") (pintype "passive"))
      (node (ref "C142") (pin "2") (pinfunction "2_2") (pintype "passive"))
      (node (ref "C143") (pin "2") (pinfunction "2_2") (pintype "passive"))
      (node (ref "C145") (pin "2") (pinfunction "2_2") (pintype "passive"))
      (node (ref "C147") (pin "2") (pinfunction "2_2") (pintype "passive"))
      (node (ref "C148") (pin "2") (pinfunction "2_2") (pintype "passive"))
      (node (ref "C149") (pin "2") (pinfunction "2_2") (pintype "passive"))
      (node (ref "C150") (pin "2") (pinfunction "2_2") (pintype "passive"))
      (node (ref "C151") (pin "2") (pinfunction "2_2") (pintype "passive"))
      (node (ref "C152") (pin "2") (pinfunction "2_2") (pintype "passive"))
      (node (ref "C153") (pin "2") (pinfunction "2_2") (pintype "passive"))
      (node (ref "C154") (pin "2") (pinfunction "2_2") (pintype "passive"))
      (node (ref "C156") (pin "2") (pinfunction "2_2") (pintype "passive"))
      (node (ref "C157") (pin "2") (pinfunction "2_2") (pintype "passive"))
      (node (ref "C158") (pin "2") (pinfunction "2_2") (pintype "passive"))
      (node (ref "C159") (pin "2") (pinfunction "2_2") (pintype "passive"))
      (node (ref "C160") (pin "2") (pinfunction "2_2") (pintype "passive"))
      (node (ref "C161") (pin "2") (pinfunction "2_2") (pintype "passive"))
      (node (ref "DD1") (pin "A20") (pinfunction "VCCO_35_A20") (pintype "passive"))
      (node (ref "DD1") (pin "AA20") (pinfunction "VCCO_33_AA20") (pintype "passive"))
      (node (ref "DD1") (pin "AB13") (pinfunction "VCCO_33_AB13") (pintype "passive"))
      (node (ref "DD1") (pin "C16") (pinfunction "VCCO_35_C16") (pintype "passive"))
      (node (ref "DD1") (pin "D19") (pinfunction "VCCO_35_D19") (pintype "passive"))
      (node (ref "DD1") (pin "E22") (pinfunction "VCCO_35_E22") (pintype "passive"))
      (node (ref "DD1") (pin "F15") (pinfunction "VCCO_35_F15") (pintype "passive"))
      (node (ref "DD1") (pin "G18") (pinfunction "VCCO_35_G18") (pintype "passive"))
      (node (ref "DD1") (pin "H21") (pinfunction "VCCO_35_H21") (pintype "passive"))
      (node (ref "DD1") (pin "K17") (pinfunction "VCCO_34_K17") (pintype "passive"))
      (node (ref "DD1") (pin "L20") (pinfunction "VCCO_34_L20") (pintype "passive"))
      (node (ref "DD1") (pin "N16") (pinfunction "VCCO_34_N16") (pintype "passive"))
      (node (ref "DD1") (pin "P19") (pinfunction "VCCO_34_P19") (pintype "passive"))
      (node (ref "DD1") (pin "R22") (pinfunction "VCCO_34_R22") (pintype "passive"))
      (node (ref "DD1") (pin "T15") (pinfunction "VCCO_34_T15") (pintype "passive"))
      (node (ref "DD1") (pin "U18") (pinfunction "VCCO_33_U18") (pintype "passive"))
      (node (ref "DD1") (pin "V21") (pinfunction "VCCO_33_V21") (pintype "passive"))
      (node (ref "DD1") (pin "W14") (pinfunction "VCCO_33_W14") (pintype "passive"))
      (node (ref "DD1") (pin "Y17") (pinfunction "VCCO_33_Y17") (pintype "passive"))
      (node (ref "R61") (pin "2") (pinfunction "2_2") (pintype "passive"))
    )
    (net (code "195") (name "VDD_3V3") (class "Default")
      (node (ref "C132") (pin "2") (pinfunction "2_2") (pintype "passive"))
      (node (ref "C133") (pin "2") (pinfunction "2_2") (pintype "passive"))
      (node (ref "C136") (pin "2") (pinfunction "2_2") (pintype "passive"))
      (node (ref "C140") (pin "2") (pinfunction "2_2") (pintype "passive"))
      (node (ref "C144") (pin "2") (pinfunction "2_2") (pintype "passive"))
      (node (ref "DD1") (pin "AA10") (pinfunction "VCCO_13_AA10") (pintype "passive"))
      (node (ref "DD1") (pin "AB3") (pinfunction "VCCO_13_AB3") (pintype "passive"))
      (node (ref "DD1") (pin "T5") (pinfunction "VCCO_13_T5") (pintype "passive"))
      (node (ref "DD1") (pin "U8") (pinfunction "VCCO_13_U8") (pintype "passive"))
      (node (ref "DD1") (pin "V11") (pinfunction "VCCO_13_V11") (pintype "passive"))
      (node (ref "DD1") (pin "W4") (pinfunction "VCCO_13_W4") (pintype "passive"))
      (node (ref "DD1") (pin "Y7") (pinfunction "VCCO_13_Y7") (pintype "passive"))
      (node (ref "L17") (pin "1") (pinfunction "1_1") (pintype "passive"))
    )
    (net (code "196") (name "unconnected-(DD1B-IO_0_13-PadR7)") (class "Default")
      (node (ref "DD1") (pin "R7") (pinfunction "IO_0_13_R7") (pintype "passive"))
    )
    (net (code "197") (name "unconnected-(DD1B-IO_25_13-PadU7)") (class "Default")
      (node (ref "DD1") (pin "U7") (pinfunction "IO_25_13_U7") (pintype "passive"))
    )
    (net (code "198") (name "unconnected-(DD1B-IO_L1P_T0_13-PadV10)") (class "Default")
      (node (ref "DD1") (pin "V10") (pinfunction "IO_L1P_T0_13_V10") (pintype "passive"))
    )
    (net (code "199") (name "unconnected-(DD1B-IO_L3N_T0_DQS_13-PadW10)") (class "Default")
      (node (ref "DD1") (pin "W10") (pinfunction "IO_L3N_T0_DQS_13_W10") (pintype "passive"))
    )
    (net (code "200") (name "unconnected-(DD1B-IO_L3P_T0_DQS_13-PadW11)") (class "Default")
      (node (ref "DD1") (pin "W11") (pinfunction "IO_L3P_T0_DQS_13_W11") (pintype "passive"))
    )
    (net (code "201") (name "unconnected-(DD1B-IO_L4N_T0_13-PadW12)") (class "Default")
      (node (ref "DD1") (pin "W12") (pinfunction "IO_L4N_T0_13_W12") (pintype "passive"))
    )
    (net (code "202") (name "unconnected-(DD1B-IO_L4P_T0_13-PadV12)") (class "Default")
      (node (ref "DD1") (pin "V12") (pinfunction "IO_L4P_T0_13_V12") (pintype "passive"))
    )
    (net (code "203") (name "unconnected-(DD1B-IO_L5P_T0_13-PadU12)") (class "Default")
      (node (ref "DD1") (pin "U12") (pinfunction "IO_L5P_T0_13_U12") (pintype "passive"))
    )
    (net (code "204") (name "unconnected-(DD1B-IO_L6N_T0_VREF_13-PadU9)") (class "Default")
      (node (ref "DD1") (pin "U9") (pinfunction "IO_L6N_T0_VREF_13_U9") (pintype "passive"))
    )
    (net (code "205") (name "unconnected-(DD1B-IO_L10N_T1_13-PadY10)") (class "Default")
      (node (ref "DD1") (pin "Y10") (pinfunction "IO_L10N_T1_13_Y10") (pintype "passive"))
    )
    (net (code "206") (name "unconnected-(DD1B-IO_L11N_T1_SRCC_13-PadAA8)") (class "Default")
      (node (ref "DD1") (pin "AA8") (pinfunction "IO_L11N_T1_SRCC_13_AA8") (pintype "passive"))
    )
    (net (code "207") (name "unconnected-(DD1B-IO_L11P_T1_SRCC_13-PadAA9)") (class "Default")
      (node (ref "DD1") (pin "AA9") (pinfunction "IO_L11P_T1_SRCC_13_AA9") (pintype "passive"))
    )
    (net (code "208") (name "unconnected-(DD1B-IO_L19N_T3_VREF_13-PadT6)") (class "Default")
      (node (ref "DD1") (pin "T6") (pinfunction "IO_L19N_T3_VREF_13_T6") (pintype "passive"))
    )
    (net (code "209") (name "unconnected-(DD1B-IO_L19P_T3_13-PadR6)") (class "Default")
      (node (ref "DD1") (pin "R6") (pinfunction "IO_L19P_T3_13_R6") (pintype "passive"))
    )
    (net (code "210") (name "unconnected-(DD1B-IO_L20N_T3_13-PadU4)") (class "Default")
      (node (ref "DD1") (pin "U4") (pinfunction "IO_L20N_T3_13_U4") (pintype "passive"))
    )
    (net (code "211") (name "unconnected-(DD1B-IO_L20P_T3_13-PadT4)") (class "Default")
      (node (ref "DD1") (pin "T4") (pinfunction "IO_L20P_T3_13_T4") (pintype "passive"))
    )
    (net (code "212") (name "unconnected-(DD1B-IO_L21N_T3_DQS_13-PadV4)") (class "Default")
      (node (ref "DD1") (pin "V4") (pinfunction "IO_L21N_T3_DQS_13_V4") (pintype "passive"))
    )
    (net (code "213") (name "unconnected-(DD1B-IO_L22N_T3_13-PadU5)") (class "Default")
      (node (ref "DD1") (pin "U5") (pinfunction "IO_L22N_T3_13_U5") (pintype "passive"))
    )
    (net (code "214") (name "unconnected-(DD1B-IO_L22P_T3_13-PadU6)") (class "Default")
      (node (ref "DD1") (pin "U6") (pinfunction "IO_L22P_T3_13_U6") (pintype "passive"))
    )
    (net (code "215") (name "unconnected-(DD1C-IO_0_33-PadU19)") (class "Default")
      (node (ref "DD1") (pin "U19") (pinfunction "IO_0_33_U19") (pintype "passive"))
    )
    (net (code "216") (name "unconnected-(DD1C-IO_25_33-PadU14)") (class "Default")
      (node (ref "DD1") (pin "U14") (pinfunction "IO_25_33_U14") (pintype "passive"))
    )
    (net (code "217") (name "unconnected-(DD1C-IO_L9N_T1_DQS_33-PadY21)") (class "Default")
      (node (ref "DD1") (pin "Y21") (pinfunction "IO_L9N_T1_DQS_33_Y21") (pintype "passive"))
    )
    (net (code "218") (name "unconnected-(DD1C-IO_L9P_T1_DQS_33-PadY20)") (class "Default")
      (node (ref "DD1") (pin "Y20") (pinfunction "IO_L9P_T1_DQS_33_Y20") (pintype "passive"))
    )
    (net (code "219") (name "unconnected-(DD1C-IO_L12N_T1_MRCC_33-PadAA18)") (class "Default")
      (node (ref "DD1") (pin "AA18") (pinfunction "IO_L12N_T1_MRCC_33_AA18") (pintype "passive"))
    )
    (net (code "220") (name "unconnected-(DD1C-IO_L12P_T1_MRCC_33-PadY18)") (class "Default")
      (node (ref "DD1") (pin "Y18") (pinfunction "IO_L12P_T1_MRCC_33_Y18") (pintype "passive"))
    )
    (net (code "221") (name "unconnected-(DD1C-IO_L13N_T2_MRCC_33-PadW18)") (class "Default")
      (node (ref "DD1") (pin "W18") (pinfunction "IO_L13N_T2_MRCC_33_W18") (pintype "passive"))
    )
    (net (code "222") (name "unconnected-(DD1C-IO_L13P_T2_MRCC_33-PadW17)") (class "Default")
      (node (ref "DD1") (pin "W17") (pinfunction "IO_L13P_T2_MRCC_33_W17") (pintype "passive"))
    )
    (net (code "223") (name "unconnected-(DD1C-IO_L19N_T3_VREF_33-PadV15)") (class "Default")
      (node (ref "DD1") (pin "V15") (pinfunction "IO_L19N_T3_VREF_33_V15") (pintype "passive"))
    )
    (net (code "224") (name "unconnected-(DD1C-IO_L21N_T3_DQS_33-PadY15)") (class "Default")
      (node (ref "DD1") (pin "Y15") (pinfunction "IO_L21N_T3_DQS_33_Y15") (pintype "passive"))
    )
    (net (code "225") (name "unconnected-(DD1C-IO_L21P_T3_DQS_33-PadW15)") (class "Default")
      (node (ref "DD1") (pin "W15") (pinfunction "IO_L21P_T3_DQS_33_W15") (pintype "passive"))
    )
    (net (code "226") (name "unconnected-(DD1D-IO_0_34-PadH15)") (class "Default")
      (node (ref "DD1") (pin "H15") (pinfunction "IO_0_34_H15") (pintype "passive"))
    )
    (net (code "227") (name "unconnected-(DD1D-IO_25_34-PadR15)") (class "Default")
      (node (ref "DD1") (pin "R15") (pinfunction "IO_25_34_R15") (pintype "passive"))
    )
    (net (code "228") (name "unconnected-(DD1D-IO_L3N_T0_DQS_34-PadL16)") (class "Default")
      (node (ref "DD1") (pin "L16") (pinfunction "IO_L3N_T0_DQS_34_L16") (pintype "passive"))
    )
    (net (code "229") (name "unconnected-(DD1D-IO_L14N_T2_SRCC_34-PadN20)") (class "Default")
      (node (ref "DD1") (pin "N20") (pinfunction "IO_L14N_T2_SRCC_34_N20") (pintype "passive"))
    )
    (net (code "230") (name "unconnected-(DD1D-IO_L14P_T2_SRCC_34-PadN19)") (class "Default")
      (node (ref "DD1") (pin "N19") (pinfunction "IO_L14P_T2_SRCC_34_N19") (pintype "passive"))
    )
    (net (code "231") (name "unconnected-(DD1D-IO_L19N_T3_VREF_34-PadP15)") (class "Default")
      (node (ref "DD1") (pin "P15") (pinfunction "IO_L19N_T3_VREF_34_P15") (pintype "passive"))
    )
    (net (code "232") (name "unconnected-(DD1D-IO_L19P_T3_34-PadN15)") (class "Default")
      (node (ref "DD1") (pin "N15") (pinfunction "IO_L19P_T3_34_N15") (pintype "passive"))
    )
    (net (code "233") (name "unconnected-(DD1D-IO_L21N_T3_DQS_34-PadT17)") (class "Default")
      (node (ref "DD1") (pin "T17") (pinfunction "IO_L21N_T3_DQS_34_T17") (pintype "passive"))
    )
    (net (code "234") (name "unconnected-(DD1D-IO_L22N_T3_34-PadT19)") (class "Default")
      (node (ref "DD1") (pin "T19") (pinfunction "IO_L22N_T3_34_T19") (pintype "passive"))
    )
    (net (code "235") (name "unconnected-(DD1D-IO_L22P_T3_34-PadR19)") (class "Default")
      (node (ref "DD1") (pin "R19") (pinfunction "IO_L22P_T3_34_R19") (pintype "passive"))
    )
    (net (code "236") (name "unconnected-(DD1D-IO_L24N_T3_34-PadR16)") (class "Default")
      (node (ref "DD1") (pin "R16") (pinfunction "IO_L24N_T3_34_R16") (pintype "passive"))
    )
    (net (code "237") (name "unconnected-(DD1D-IO_L24P_T3_34-PadP16)") (class "Default")
      (node (ref "DD1") (pin "P16") (pinfunction "IO_L24P_T3_34_P16") (pintype "passive"))
    )
    (net (code "238") (name "unconnected-(DD1E-IO_25_35-PadH18)") (class "Default")
      (node (ref "DD1") (pin "H18") (pinfunction "IO_25_35_H18") (pintype "passive"))
    )
    (net (code "239") (name "unconnected-(DD1E-IO_L1N_T0_AD0N_35-PadE16)") (class "Default")
      (node (ref "DD1") (pin "E16") (pinfunction "IO_L1N_T0_AD0N_35_E16") (pintype "passive"))
    )
    (net (code "240") (name "unconnected-(DD1E-IO_L1P_T0_AD0P_35-PadF16)") (class "Default")
      (node (ref "DD1") (pin "F16") (pinfunction "IO_L1P_T0_AD0P_35_F16") (pintype "passive"))
    )
    (net (code "241") (name "unconnected-(DD1E-IO_L3N_T0_DQS_AD1N_35-PadD15)") (class "Default")
      (node (ref "DD1") (pin "D15") (pinfunction "IO_L3N_T0_DQS_AD1N_35_D15") (pintype "passive"))
    )
    (net (code "242") (name "unconnected-(DD1E-IO_L3P_T0_DQS_AD1P_35-PadE15)") (class "Default")
      (node (ref "DD1") (pin "E15") (pinfunction "IO_L3P_T0_DQS_AD1P_35_E15") (pintype "passive"))
    )
    (net (code "243") (name "unconnected-(DD1E-IO_L4N_T0_35-PadG16)") (class "Default")
      (node (ref "DD1") (pin "G16") (pinfunction "IO_L4N_T0_35_G16") (pintype "passive"))
    )
    (net (code "244") (name "unconnected-(DD1E-IO_L4P_T0_35-PadG15)") (class "Default")
      (node (ref "DD1") (pin "G15") (pinfunction "IO_L4P_T0_35_G15") (pintype "passive"))
    )
    (net (code "245") (name "unconnected-(DD1E-IO_L6N_T0_VREF_35-PadF17)") (class "Default")
      (node (ref "DD1") (pin "F17") (pinfunction "IO_L6N_T0_VREF_35_F17") (pintype "passive"))
    )
    (net (code "246") (name "unconnected-(DD1E-IO_L6P_T0_35-PadG17)") (class "Default")
      (node (ref "DD1") (pin "G17") (pinfunction "IO_L6P_T0_35_G17") (pintype "passive"))
    )
    (net (code "247") (name "unconnected-(DD1E-IO_L19N_T3_VREF_35-PadH20)") (class "Default")
      (node (ref "DD1") (pin "H20") (pinfunction "IO_L19N_T3_VREF_35_H20") (pintype "passive"))
    )
    (net (code "248") (name "unconnected-(DD1E-IO_L19P_T3_35-PadH19)") (class "Default")
      (node (ref "DD1") (pin "H19") (pinfunction "IO_L19P_T3_35_H19") (pintype "passive"))
    )
    (net (code "249") (name "unconnected-(DD1E-IO_L20N_T3_AD6N_35-PadF19)") (class "Default")
      (node (ref "DD1") (pin "F19") (pinfunction "IO_L20N_T3_AD6N_35_F19") (pintype "passive"))
    )
    (net (code "250") (name "unconnected-(DD1E-IO_L20P_T3_AD6P_35-PadG19)") (class "Default")
      (node (ref "DD1") (pin "G19") (pinfunction "IO_L20P_T3_AD6P_35_G19") (pintype "passive"))
    )
    (net (code "251") (name "unconnected-(DD1E-IO_L22N_T3_AD7N_35-PadG21)") (class "Default")
      (node (ref "DD1") (pin "G21") (pinfunction "IO_L22N_T3_AD7N_35_G21") (pintype "passive"))
    )
    (net (code "252") (name "unconnected-(DD1E-IO_L22P_T3_AD7P_35-PadG20)") (class "Default")
      (node (ref "DD1") (pin "G20") (pinfunction "IO_L22P_T3_AD7P_35_G20") (pintype "passive"))
    )
    (net (code "253") (name "unconnected-(DD7A-LDO_O-Pad43)") (class "Default")
      (node (ref "DD7") (pin "43") (pinfunction "LDO_O_43") (pintype "output"))
    )
    (net (code "254") (name "unconnected-(DD7B-NC-Pad13)") (class "Default")
      (node (ref "DD7") (pin "13") (pinfunction "NC_13") (pintype "passive"))
    )
    (net (code "255") (name "unconnected-(DD7B-NC-Pad47)") (class "Default")
      (node (ref "DD7") (pin "47") (pinfunction "NC_47") (pintype "passive"))
    )
  )
)
